# ra8875_ez80_2_1.net
KiCad netlist of a schematic drawn in EAGLE
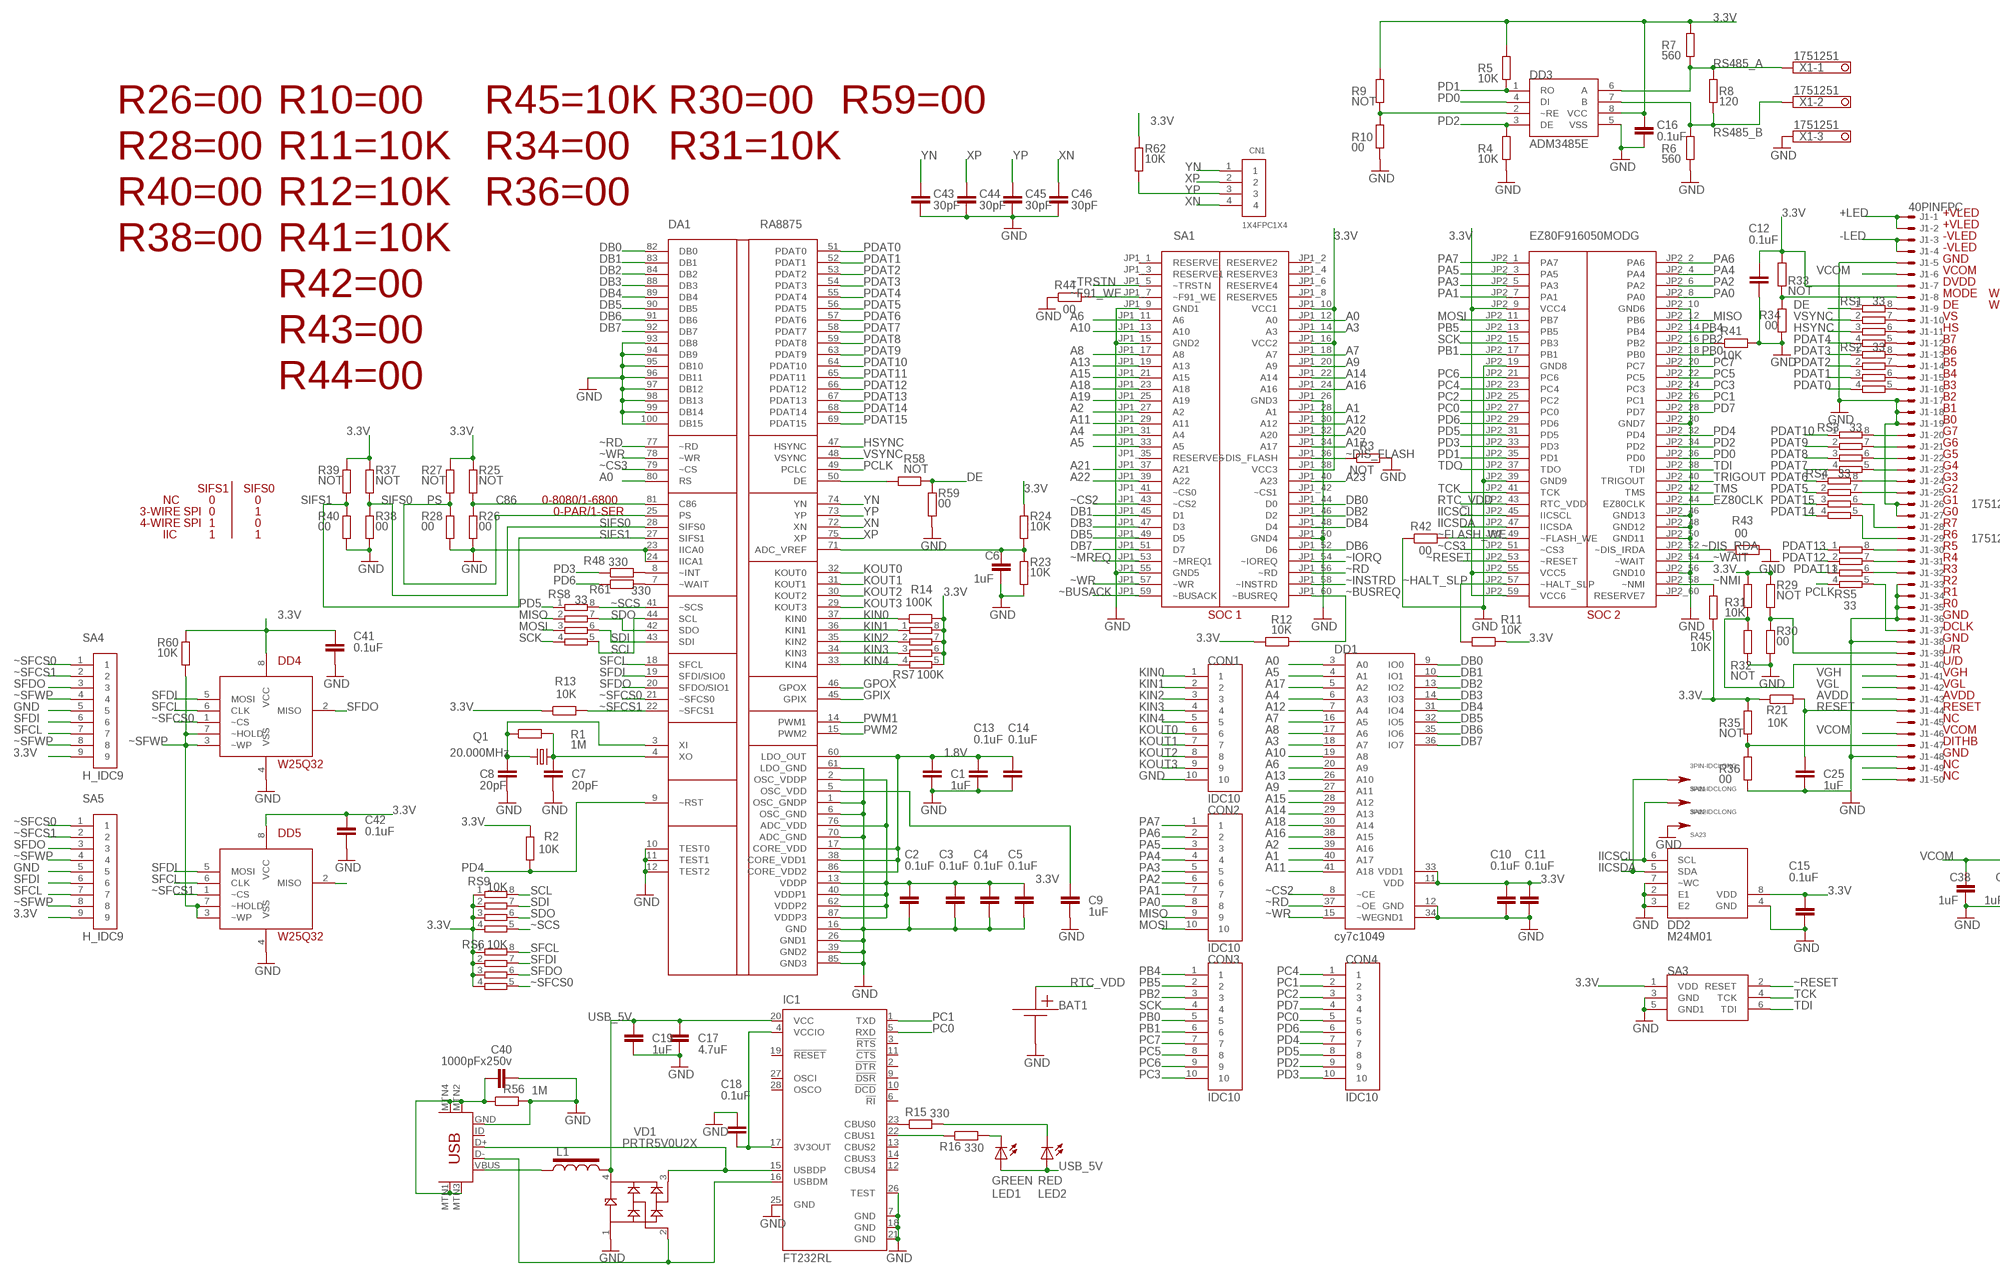
[diagram p0: schematic, sheet 1, part 1 of 2]
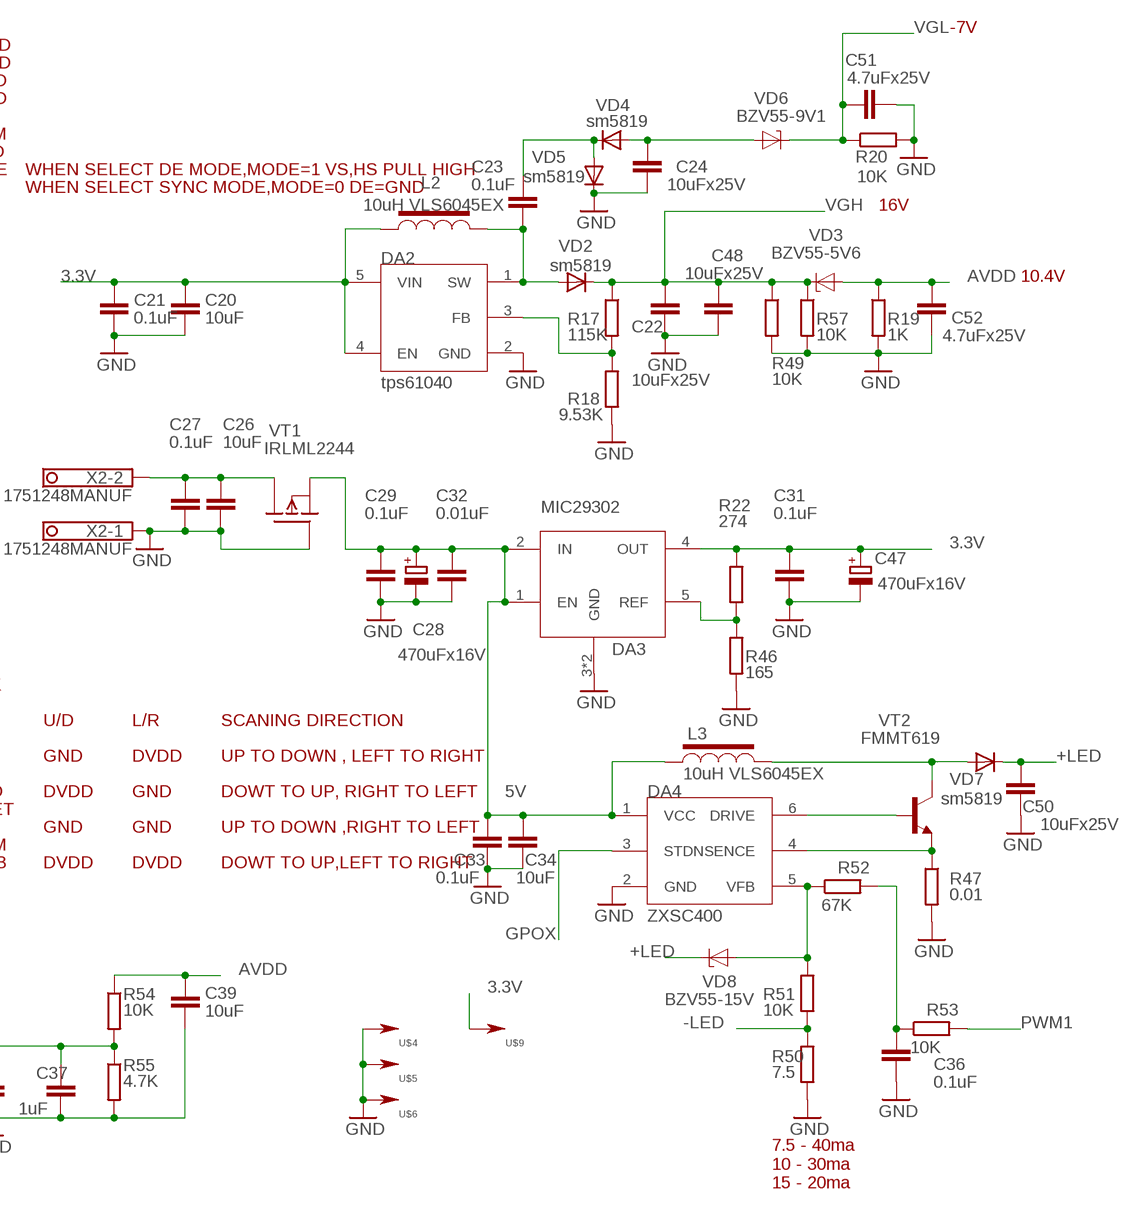
[diagram p1: schematic, sheet 1, part 2 of 2]

(export (version "E")
  (design (tool "Eeschema 10.0.6"))
  (components
    (comp (ref "BAT1")
      (value "EECF5R5U155")
      (footprint "eagle-import:EECF5R5U155")
      (libsource (lib "eagle-import") (part "EECF5R5U155"))
    )
    (comp (ref "C1")
      (value "1uF")
      (footprint "eagle-import:C0603")
      (libsource (lib "eagle-import") (part "C-EUC0603"))
    )
    (comp (ref "C2")
      (value "0.1uF")
      (footprint "eagle-import:C0603")
      (libsource (lib "eagle-import") (part "C-EUC0603"))
    )
    (comp (ref "C3")
      (value "0.1uF")
      (footprint "eagle-import:C0603")
      (libsource (lib "eagle-import") (part "C-EUC0603"))
    )
    (comp (ref "C4")
      (value "0.1uF")
      (footprint "eagle-import:C0603")
      (libsource (lib "eagle-import") (part "C-EUC0603"))
    )
    (comp (ref "C5")
      (value "0.1uF")
      (footprint "eagle-import:C0603")
      (libsource (lib "eagle-import") (part "C-EUC0603"))
    )
    (comp (ref "C6")
      (value "1uF")
      (footprint "eagle-import:C0603")
      (libsource (lib "eagle-import") (part "C-EUC0603"))
    )
    (comp (ref "C7")
      (value "20pF")
      (footprint "eagle-import:C0805")
      (libsource (lib "eagle-import") (part "C-EUC0805"))
    )
    (comp (ref "C8")
      (value "20pF")
      (footprint "eagle-import:C0805")
      (libsource (lib "eagle-import") (part "C-EUC0805"))
    )
    (comp (ref "C9")
      (value "1uF")
      (footprint "eagle-import:C0603")
      (libsource (lib "eagle-import") (part "C-EUC0603"))
    )
    (comp (ref "C10")
      (value "0.1uF")
      (footprint "eagle-import:C0603")
      (libsource (lib "eagle-import") (part "C-EUC0603"))
    )
    (comp (ref "C11")
      (value "0.1uF")
      (footprint "eagle-import:C0603")
      (libsource (lib "eagle-import") (part "C-EUC0603"))
    )
    (comp (ref "C12")
      (value "0.1uF")
      (footprint "eagle-import:C0603")
      (libsource (lib "eagle-import") (part "C-EUC0603"))
    )
    (comp (ref "C13")
      (value "0.1uF")
      (footprint "eagle-import:C0603")
      (libsource (lib "eagle-import") (part "C-EUC0603"))
    )
    (comp (ref "C14")
      (value "0.1uF")
      (footprint "eagle-import:C0603")
      (libsource (lib "eagle-import") (part "C-EUC0603"))
    )
    (comp (ref "C15")
      (value "0.1uF")
      (footprint "eagle-import:C0603")
      (libsource (lib "eagle-import") (part "C-EUC0603"))
    )
    (comp (ref "C16")
      (value "0.1uF")
      (footprint "eagle-import:C0603")
      (libsource (lib "eagle-import") (part "C-EUC0603"))
    )
    (comp (ref "C17")
      (value "4.7uF")
      (footprint "eagle-import:C0805")
      (libsource (lib "eagle-import") (part "C-EUC0805"))
    )
    (comp (ref "C18")
      (value "0.1uF")
      (footprint "eagle-import:C0603")
      (libsource (lib "eagle-import") (part "C-EUC0603"))
    )
    (comp (ref "C19")
      (value "1uF")
      (footprint "eagle-import:C0603")
      (libsource (lib "eagle-import") (part "C-EUC0603"))
    )
    (comp (ref "C20")
      (value "10uF")
      (footprint "eagle-import:C1206")
      (libsource (lib "eagle-import") (part "C-EUC1206"))
    )
    (comp (ref "C21")
      (value "0.1uF")
      (footprint "eagle-import:C0805")
      (libsource (lib "eagle-import") (part "C-EUC0805"))
    )
    (comp (ref "C22")
      (value "10uFx25V")
      (footprint "eagle-import:C1206")
      (libsource (lib "eagle-import") (part "C-EUC1206"))
    )
    (comp (ref "C23")
      (value "0.1uF")
      (footprint "eagle-import:C1206")
      (libsource (lib "eagle-import") (part "C-EUC1206"))
    )
    (comp (ref "C24")
      (value "10uFx25V")
      (footprint "eagle-import:C1206")
      (libsource (lib "eagle-import") (part "C-EUC1206"))
    )
    (comp (ref "C25")
      (value "1uF")
      (footprint "eagle-import:C0603")
      (libsource (lib "eagle-import") (part "C-EUC0603"))
    )
    (comp (ref "C26")
      (value "10uF")
      (footprint "eagle-import:C1206")
      (libsource (lib "eagle-import") (part "C-EUC1206"))
    )
    (comp (ref "C27")
      (value "0.1uF")
      (footprint "eagle-import:C0805")
      (libsource (lib "eagle-import") (part "C-EUC0805"))
    )
    (comp (ref "C28")
      (value "470uFx16V")
      (footprint "eagle-import:SMC_D")
      (libsource (lib "eagle-import") (part "CPOL-EUSMCD"))
    )
    (comp (ref "C29")
      (value "0.1uF")
      (footprint "eagle-import:C0805")
      (libsource (lib "eagle-import") (part "C-EUC0805"))
    )
    (comp (ref "C31")
      (value "0.1uF")
      (footprint "eagle-import:C0805")
      (libsource (lib "eagle-import") (part "C-EUC0805"))
    )
    (comp (ref "C32")
      (value "0.01uF")
      (footprint "eagle-import:C0805")
      (libsource (lib "eagle-import") (part "C-EUC0805"))
    )
    (comp (ref "C33")
      (value "0.1uF")
      (footprint "eagle-import:C0805")
      (libsource (lib "eagle-import") (part "C-EUC0805"))
    )
    (comp (ref "C34")
      (value "10uF")
      (footprint "eagle-import:C1206")
      (libsource (lib "eagle-import") (part "C-EUC1206"))
    )
    (comp (ref "C36")
      (value "0.1uF")
      (footprint "eagle-import:C0805")
      (libsource (lib "eagle-import") (part "C-EUC0805"))
    )
    (comp (ref "C37")
      (value "1uF")
      (footprint "eagle-import:C0603")
      (libsource (lib "eagle-import") (part "C-EUC0603"))
    )
    (comp (ref "C38")
      (value "1uF")
      (footprint "eagle-import:C0603")
      (libsource (lib "eagle-import") (part "C-EUC0603"))
    )
    (comp (ref "C39")
      (value "10uF")
      (footprint "eagle-import:C1206")
      (libsource (lib "eagle-import") (part "C-EUC1206"))
    )
    (comp (ref "C40")
      (value "1000pFx250v")
      (footprint "eagle-import:C1812")
      (libsource (lib "eagle-import") (part "C-EUC1812"))
    )
    (comp (ref "C41")
      (value "0.1uF")
      (footprint "eagle-import:C0603")
      (libsource (lib "eagle-import") (part "C-EUC0603"))
    )
    (comp (ref "C42")
      (value "0.1uF")
      (footprint "eagle-import:C0603")
      (libsource (lib "eagle-import") (part "C-EUC0603"))
    )
    (comp (ref "C43")
      (value "30pF")
      (footprint "eagle-import:C0603")
      (libsource (lib "eagle-import") (part "C-EUC0603"))
    )
    (comp (ref "C44")
      (value "30pF")
      (footprint "eagle-import:C0603")
      (libsource (lib "eagle-import") (part "C-EUC0603"))
    )
    (comp (ref "C45")
      (value "30pF")
      (footprint "eagle-import:C0603")
      (libsource (lib "eagle-import") (part "C-EUC0603"))
    )
    (comp (ref "C46")
      (value "30pF")
      (footprint "eagle-import:C0603")
      (libsource (lib "eagle-import") (part "C-EUC0603"))
    )
    (comp (ref "C47")
      (value "470uFx16V")
      (footprint "eagle-import:SMC_D")
      (libsource (lib "eagle-import") (part "CPOL-EUSMCD"))
    )
    (comp (ref "C48")
      (value "10uFx25V")
      (footprint "eagle-import:C1206")
      (libsource (lib "eagle-import") (part "C-EUC1206"))
    )
    (comp (ref "C50")
      (value "10uFx25V")
      (footprint "eagle-import:C1206")
      (libsource (lib "eagle-import") (part "C-EUC1206"))
    )
    (comp (ref "C51")
      (value "4.7uFx25V")
      (footprint "eagle-import:C1206")
      (libsource (lib "eagle-import") (part "C-EUC1206"))
    )
    (comp (ref "C52")
      (value "4.7uFx25V")
      (footprint "eagle-import:C1206")
      (libsource (lib "eagle-import") (part "C-EUC1206"))
    )
    (comp (ref "CN1")
      (value "1X4FPC1X4")
      (footprint "eagle-import:FPC_1MM-4")
      (libsource (lib "eagle-import") (part "1X4FPC1X4"))
    )
    (comp (ref "CON1")
      (value "IDC10")
      (footprint "eagle-import:IDC10")
      (libsource (lib "eagle-import") (part "IDC10"))
    )
    (comp (ref "CON2")
      (value "IDC10")
      (footprint "eagle-import:IDC10")
      (libsource (lib "eagle-import") (part "IDC10"))
    )
    (comp (ref "CON3")
      (value "IDC10")
      (footprint "eagle-import:IDC10")
      (libsource (lib "eagle-import") (part "IDC10"))
    )
    (comp (ref "CON4")
      (value "IDC10")
      (footprint "eagle-import:IDC10")
      (libsource (lib "eagle-import") (part "IDC10"))
    )
    (comp (ref "DA1")
      (value "RA8875")
      (footprint "eagle-import:LQFP100")
      (libsource (lib "eagle-import") (part "RA8875"))
    )
    (comp (ref "DA2")
      (value "tps61040")
      (footprint "eagle-import:SOT23-5L")
      (libsource (lib "eagle-import") (part "TPS61040"))
    )
    (comp (ref "DA3")
      (value "MIC29302")
      (footprint "eagle-import:TO263-5")
      (libsource (lib "eagle-import") (part "MIC29302TO263-5"))
    )
    (comp (ref "DA4")
      (value "ZXSC400")
      (footprint "eagle-import:SOT23-6L")
      (libsource (lib "eagle-import") (part "ZXSC400LONG"))
    )
    (comp (ref "DD1")
      (value "cy7c1049")
      (footprint "eagle-import:TSOP_Z44_II")
      (libsource (lib "eagle-import") (part "CY7C1049DV33"))
    )
    (comp (ref "DD2")
      (value "M24M01")
      (footprint "eagle-import:SOIC8")
      (libsource (lib "eagle-import") (part "M24M01SOIC8"))
    )
    (comp (ref "DD3")
      (value "ADM3485E")
      (footprint "eagle-import:SO8")
      (libsource (lib "eagle-import") (part "ADM3485ESOIC8"))
    )
    (comp (ref "DD4")
      (value "W25Q32")
      (footprint "eagle-import:SOIC-208")
      (libsource (lib "eagle-import") (part "W25Q32SOIC208"))
    )
    (comp (ref "DD5")
      (value "W25Q32")
      (footprint "eagle-import:SOIC-208")
      (libsource (lib "eagle-import") (part "W25Q32SOIC208"))
    )
    (comp (ref "IC1")
      (value "FT232RL")
      (footprint "eagle-import:SSOP28")
      (libsource (lib "eagle-import") (part "FT232RL"))
    )
    (comp (ref "J1")
      (value "40PINFPC")
      (footprint "eagle-import:4-1734839-0")
      (libsource (lib "eagle-import") (part "40PINFPC"))
    )
    (comp (ref "L1")
      (value "USB_INDUCTOR")
      (footprint "eagle-import:R0805")
      (libsource (lib "eagle-import") (part "USB_INDUCTOR"))
    )
    (comp (ref "L2")
      (value "10uH VLS6045EX")
      (footprint "eagle-import:VLS6045")
      (libsource (lib "eagle-import") (part "INDUCTOR6045"))
    )
    (comp (ref "L3")
      (value "10uH VLS6045EX")
      (footprint "eagle-import:VLS6045")
      (libsource (lib "eagle-import") (part "INDUCTOR6045"))
    )
    (comp (ref "LED1")
      (value "GREEN")
      (footprint "eagle-import:CHIPLED_1206")
      (libsource (lib "eagle-import") (part "LEDCHIPLED_1206"))
    )
    (comp (ref "LED2")
      (value "RED")
      (footprint "eagle-import:CHIPLED_1206")
      (libsource (lib "eagle-import") (part "LEDCHIPLED_1206"))
    )
    (comp (ref "Q1")
      (value "20.000MHz")
      (footprint "eagle-import:HC49U70")
      (libsource (lib "eagle-import") (part "CRYSTALHC49U70"))
    )
    (comp (ref "R1")
      (value "1M")
      (footprint "eagle-import:R0603")
      (libsource (lib "eagle-import") (part "R-EU_R0603"))
    )
    (comp (ref "R2")
      (value "10K")
      (footprint "eagle-import:R0603")
      (libsource (lib "eagle-import") (part "R-EU_R0603"))
    )
    (comp (ref "R3")
      (value "NOT")
      (footprint "eagle-import:R0603")
      (libsource (lib "eagle-import") (part "R-EU_R0603"))
    )
    (comp (ref "R4")
      (value "10K")
      (footprint "eagle-import:R0603")
      (libsource (lib "eagle-import") (part "R-EU_R0603"))
    )
    (comp (ref "R5")
      (value "10K")
      (footprint "eagle-import:R0603")
      (libsource (lib "eagle-import") (part "R-EU_R0603"))
    )
    (comp (ref "R6")
      (value "560")
      (footprint "eagle-import:R0603")
      (libsource (lib "eagle-import") (part "R-EU_R0603"))
    )
    (comp (ref "R7")
      (value "560")
      (footprint "eagle-import:R0603")
      (libsource (lib "eagle-import") (part "R-EU_R0603"))
    )
    (comp (ref "R8")
      (value "120")
      (footprint "eagle-import:R0603")
      (libsource (lib "eagle-import") (part "R-EU_R0603"))
    )
    (comp (ref "R9")
      (value "NOT")
      (footprint "eagle-import:R0603")
      (libsource (lib "eagle-import") (part "R-EU_R0603"))
    )
    (comp (ref "R10")
      (value "00")
      (footprint "eagle-import:R0603")
      (libsource (lib "eagle-import") (part "R-EU_R0603"))
    )
    (comp (ref "R11")
      (value "10K")
      (footprint "eagle-import:R0603")
      (libsource (lib "eagle-import") (part "R-EU_R0603"))
    )
    (comp (ref "R12")
      (value "10K")
      (footprint "eagle-import:R0603")
      (libsource (lib "eagle-import") (part "R-EU_R0603"))
    )
    (comp (ref "R13")
      (value "10K")
      (footprint "eagle-import:R0603")
      (libsource (lib "eagle-import") (part "R-EU_R0603"))
    )
    (comp (ref "R14")
      (value "100K")
      (footprint "eagle-import:R0603")
      (libsource (lib "eagle-import") (part "R-EU_R0603"))
    )
    (comp (ref "R15")
      (value "330")
      (footprint "eagle-import:R0603")
      (libsource (lib "eagle-import") (part "R-EU_R0603"))
    )
    (comp (ref "R16")
      (value "330")
      (footprint "eagle-import:R0603")
      (libsource (lib "eagle-import") (part "R-EU_R0603"))
    )
    (comp (ref "R17")
      (value "115K")
      (footprint "eagle-import:R0805")
      (libsource (lib "eagle-import") (part "R-EU_R0805"))
    )
    (comp (ref "R18")
      (value "9.53K")
      (footprint "eagle-import:R0805")
      (libsource (lib "eagle-import") (part "R-EU_R0805"))
    )
    (comp (ref "R19")
      (value "1K")
      (footprint "eagle-import:R0805")
      (libsource (lib "eagle-import") (part "R-EU_R0805"))
    )
    (comp (ref "R20")
      (value "10K")
      (footprint "eagle-import:R0805")
      (libsource (lib "eagle-import") (part "R-EU_R0805"))
    )
    (comp (ref "R21")
      (value "10K")
      (footprint "eagle-import:R0603")
      (libsource (lib "eagle-import") (part "R-EU_R0603"))
    )
    (comp (ref "R22")
      (value "274")
      (footprint "eagle-import:R0805")
      (libsource (lib "eagle-import") (part "R-EU_R0805"))
    )
    (comp (ref "R23")
      (value "10K")
      (footprint "eagle-import:R0603")
      (libsource (lib "eagle-import") (part "R-EU_R0603"))
    )
    (comp (ref "R24")
      (value "10K")
      (footprint "eagle-import:R0603")
      (libsource (lib "eagle-import") (part "R-EU_R0603"))
    )
    (comp (ref "R25")
      (value "NOT")
      (footprint "eagle-import:R0603")
      (libsource (lib "eagle-import") (part "R-EU_R0603"))
    )
    (comp (ref "R26")
      (value "00")
      (footprint "eagle-import:R0603")
      (libsource (lib "eagle-import") (part "R-EU_R0603"))
    )
    (comp (ref "R27")
      (value "NOT")
      (footprint "eagle-import:R0603")
      (libsource (lib "eagle-import") (part "R-EU_R0603"))
    )
    (comp (ref "R28")
      (value "00")
      (footprint "eagle-import:R0603")
      (libsource (lib "eagle-import") (part "R-EU_R0603"))
    )
    (comp (ref "R29")
      (value "NOT")
      (footprint "eagle-import:R0603")
      (libsource (lib "eagle-import") (part "R-EU_R0603"))
    )
    (comp (ref "R30")
      (value "00")
      (footprint "eagle-import:R0603")
      (libsource (lib "eagle-import") (part "R-EU_R0603"))
    )
    (comp (ref "R31")
      (value "10K")
      (footprint "eagle-import:R0603")
      (libsource (lib "eagle-import") (part "R-EU_R0603"))
    )
    (comp (ref "R32")
      (value "NOT")
      (footprint "eagle-import:R0603")
      (libsource (lib "eagle-import") (part "R-EU_R0603"))
    )
    (comp (ref "R33")
      (value "NOT")
      (footprint "eagle-import:R0603")
      (libsource (lib "eagle-import") (part "R-EU_R0603"))
    )
    (comp (ref "R34")
      (value "00")
      (footprint "eagle-import:R0603")
      (libsource (lib "eagle-import") (part "R-EU_R0603"))
    )
    (comp (ref "R35")
      (value "NOT")
      (footprint "eagle-import:R0603")
      (libsource (lib "eagle-import") (part "R-EU_R0603"))
    )
    (comp (ref "R36")
      (value "00")
      (footprint "eagle-import:R0603")
      (libsource (lib "eagle-import") (part "R-EU_R0603"))
    )
    (comp (ref "R37")
      (value "NOT")
      (footprint "eagle-import:R0603")
      (libsource (lib "eagle-import") (part "R-EU_R0603"))
    )
    (comp (ref "R38")
      (value "00")
      (footprint "eagle-import:R0603")
      (libsource (lib "eagle-import") (part "R-EU_R0603"))
    )
    (comp (ref "R39")
      (value "NOT")
      (footprint "eagle-import:R0603")
      (libsource (lib "eagle-import") (part "R-EU_R0603"))
    )
    (comp (ref "R40")
      (value "00")
      (footprint "eagle-import:R0603")
      (libsource (lib "eagle-import") (part "R-EU_R0603"))
    )
    (comp (ref "R41")
      (value "10K")
      (footprint "eagle-import:R0603")
      (libsource (lib "eagle-import") (part "R-EU_R0603"))
    )
    (comp (ref "R42")
      (value "00")
      (footprint "eagle-import:R0603")
      (libsource (lib "eagle-import") (part "R-EU_R0603"))
    )
    (comp (ref "R43")
      (value "00")
      (footprint "eagle-import:R0603")
      (libsource (lib "eagle-import") (part "R-EU_R0603"))
    )
    (comp (ref "R44")
      (value "00")
      (footprint "eagle-import:R0603")
      (libsource (lib "eagle-import") (part "R-EU_R0603"))
    )
    (comp (ref "R45")
      (value "10K")
      (footprint "eagle-import:R0603")
      (libsource (lib "eagle-import") (part "R-EU_R0603"))
    )
    (comp (ref "R46")
      (value "165")
      (footprint "eagle-import:R0805")
      (libsource (lib "eagle-import") (part "R-EU_R0805"))
    )
    (comp (ref "R47")
      (value "0.01")
      (footprint "eagle-import:R2512")
      (libsource (lib "eagle-import") (part "R-EU_R2512"))
    )
    (comp (ref "R48")
      (value "330")
      (footprint "eagle-import:R0603")
      (libsource (lib "eagle-import") (part "R-EU_R0603"))
    )
    (comp (ref "R49")
      (value "10K")
      (footprint "eagle-import:R1206")
      (libsource (lib "eagle-import") (part "R-EU_R1206"))
    )
    (comp (ref "R50")
      (value "7.5")
      (footprint "eagle-import:R0805")
      (libsource (lib "eagle-import") (part "R-EU_R0805"))
    )
    (comp (ref "R51")
      (value "10K")
      (footprint "eagle-import:R0603")
      (libsource (lib "eagle-import") (part "R-EU_R0603"))
    )
    (comp (ref "R52")
      (value "67K")
      (footprint "eagle-import:R0603")
      (libsource (lib "eagle-import") (part "R-EU_R0603"))
    )
    (comp (ref "R53")
      (value "10K")
      (footprint "eagle-import:R0603")
      (libsource (lib "eagle-import") (part "R-EU_R0603"))
    )
    (comp (ref "R54")
      (value "10K")
      (footprint "eagle-import:R0603")
      (libsource (lib "eagle-import") (part "R-EU_R0603"))
    )
    (comp (ref "R55")
      (value "4.7K")
      (footprint "eagle-import:R0603")
      (libsource (lib "eagle-import") (part "R-EU_R0603"))
    )
    (comp (ref "R56")
      (value "1M")
      (footprint "eagle-import:R1206")
      (libsource (lib "eagle-import") (part "R-EU_R1206"))
    )
    (comp (ref "R57")
      (value "10K")
      (footprint "eagle-import:R1206")
      (libsource (lib "eagle-import") (part "R-EU_R1206"))
    )
    (comp (ref "R58")
      (value "NOT")
      (footprint "eagle-import:R0603")
      (libsource (lib "eagle-import") (part "R-EU_R0603"))
    )
    (comp (ref "R59")
      (value "00")
      (footprint "eagle-import:R0603")
      (libsource (lib "eagle-import") (part "R-EU_R0603"))
    )
    (comp (ref "R60")
      (value "10K")
      (footprint "eagle-import:R0603")
      (libsource (lib "eagle-import") (part "R-EU_R0603"))
    )
    (comp (ref "R61")
      (value "330")
      (footprint "eagle-import:R0603")
      (libsource (lib "eagle-import") (part "R-EU_R0603"))
    )
    (comp (ref "R62")
      (value "10K")
      (footprint "eagle-import:R0603")
      (libsource (lib "eagle-import") (part "R-EU_R0603"))
    )
    (comp (ref "RS1")
      (value "33")
      (footprint "eagle-import:CAY16-4")
      (libsource (lib "eagle-import") (part "MULTI_RESISRORCAY16-4"))
    )
    (comp (ref "RS2")
      (value "33")
      (footprint "eagle-import:CAY16-4")
      (libsource (lib "eagle-import") (part "MULTI_RESISRORCAY16-4"))
    )
    (comp (ref "RS3")
      (value "33")
      (footprint "eagle-import:CAY16-4")
      (libsource (lib "eagle-import") (part "MULTI_RESISRORCAY16-4"))
    )
    (comp (ref "RS4")
      (value "33")
      (footprint "eagle-import:CAY16-4")
      (libsource (lib "eagle-import") (part "MULTI_RESISRORCAY16-4"))
    )
    (comp (ref "RS5")
      (value "33")
      (footprint "eagle-import:CAY16-4")
      (libsource (lib "eagle-import") (part "MULTI_RESISRORCAY16-4"))
    )
    (comp (ref "RS6")
      (value "10K")
      (footprint "eagle-import:CAY16-4")
      (libsource (lib "eagle-import") (part "MULTI_RESISRORCAY16-4"))
    )
    (comp (ref "RS7")
      (value "100K")
      (footprint "eagle-import:CAY16-4")
      (libsource (lib "eagle-import") (part "MULTI_RESISRORCAY16-4"))
    )
    (comp (ref "RS8")
      (value "33")
      (footprint "eagle-import:CAY16-4")
      (libsource (lib "eagle-import") (part "MULTI_RESISRORCAY16-4"))
    )
    (comp (ref "RS9")
      (value "10K")
      (footprint "eagle-import:CAY16-4")
      (libsource (lib "eagle-import") (part "MULTI_RESISRORCAY16-4"))
    )
    (comp (ref "SA1")
      (value "EZ80F916050MODG")
      (footprint "eagle-import:EZ80F916050MODG")
      (libsource (lib "eagle-import") (part "EZ80F916050MODG"))
    )
    (comp (ref "SA2")
      (value "3PIN-IDCLONG")
      (footprint "eagle-import:3PIN-254")
      (libsource (lib "eagle-import") (part "3PIN-IDCLONG"))
    )
    (comp (ref "SA3")
      (value "ZPAKII")
      (footprint "eagle-import:ZPAKII")
      (libsource (lib "eagle-import") (part "ZPAKII"))
    )
    (comp (ref "SA4")
      (value "H_IDC9")
      (footprint "eagle-import:H_IDC8X1_27")
      (libsource (lib "eagle-import") (part "H_IDC9"))
    )
    (comp (ref "SA5")
      (value "H_IDC9")
      (footprint "eagle-import:H_IDC8X1_27")
      (libsource (lib "eagle-import") (part "H_IDC9"))
    )
    (comp (ref "U$3")
      (value "USB-MINIB-5PIN")
      (footprint "eagle-import:USB-MINIB")
      (libsource (lib "eagle-import") (part "USB-MINIB-5PIN"))
    )
    (comp (ref "U$4")
      (value "1-PIN2_54")
      (footprint "eagle-import:1_PIN_2_54")
      (libsource (lib "eagle-import") (part "1-PIN2_54"))
    )
    (comp (ref "U$5")
      (value "1-PIN2_54")
      (footprint "eagle-import:1_PIN_2_54")
      (libsource (lib "eagle-import") (part "1-PIN2_54"))
    )
    (comp (ref "U$6")
      (value "1-PIN2_54")
      (footprint "eagle-import:1_PIN_2_54")
      (libsource (lib "eagle-import") (part "1-PIN2_54"))
    )
    (comp (ref "U$9")
      (value "1-PIN2_54")
      (footprint "eagle-import:1_PIN_2_54")
      (libsource (lib "eagle-import") (part "1-PIN2_54"))
    )
    (comp (ref "VD1")
      (value "PRTR5V0U2X")
      (footprint "eagle-import:SOT143B")
      (libsource (lib "eagle-import") (part "PRTR5V0U2X"))
    )
    (comp (ref "VD2")
      (value "sm5819")
      (footprint "eagle-import:MELF-MLL41")
      (libsource (lib "eagle-import") (part "SM5819"))
    )
    (comp (ref "VD3")
      (value "BZV55-5V6")
      (footprint "eagle-import:STABILITRON")
      (libsource (lib "eagle-import") (part "STABILITRONSMD"))
    )
    (comp (ref "VD4")
      (value "sm5819")
      (footprint "eagle-import:MELF-MLL41")
      (libsource (lib "eagle-import") (part "SM5819"))
    )
    (comp (ref "VD5")
      (value "sm5819")
      (footprint "eagle-import:MELF-MLL41")
      (libsource (lib "eagle-import") (part "SM5819"))
    )
    (comp (ref "VD6")
      (value "BZV55-9V1")
      (footprint "eagle-import:STABILITRON")
      (libsource (lib "eagle-import") (part "STABILITRONSMD"))
    )
    (comp (ref "VD7")
      (value "sm5819")
      (footprint "eagle-import:MELF-MLL41")
      (libsource (lib "eagle-import") (part "SM5819"))
    )
    (comp (ref "VD8")
      (value "BZV55-15V")
      (footprint "eagle-import:STABILITRON")
      (libsource (lib "eagle-import") (part "STABILITRONSMD"))
    )
    (comp (ref "VT1")
      (value "IRLML2244")
      (footprint "eagle-import:SOT23")
      (libsource (lib "eagle-import") (part "P-MOSFETSOT23"))
    )
    (comp (ref "VT2")
      (value "FMMT619")
      (footprint "eagle-import:SOT23-BEC")
      (libsource (lib "eagle-import") (part "-NPN-SOT23-BECBC847B"))
    )
    (comp (ref "X1")
      (value "1751251")
      (footprint "eagle-import:1751251")
      (libsource (lib "eagle-import") (part "1751251"))
    )
    (comp (ref "X2")
      (value "1751248MANUF")
      (footprint "eagle-import:1751248")
      (libsource (lib "eagle-import") (part "1751248MANUF"))
    )
  )
  (nets
    (net (code "1") (name "/+LED") (class "Default")
      (node (ref "C50") (pin "1") (pinfunction "1_1") (pintype "passive"))
      (node (ref "J1") (pin "1") (pinfunction "MSV_1") (pintype "passive"))
      (node (ref "J1") (pin "2") (pinfunction "MS_2") (pintype "passive"))
      (node (ref "VD7") (pin "C") (pinfunction "C_C") (pintype "passive"))
      (node (ref "VD8") (pin "C") (pinfunction "C_C") (pintype "passive"))
    )
    (net (code "2") (name "/-LED") (class "Default")
      (node (ref "J1") (pin "3") (pinfunction "MS_3") (pintype "passive"))
      (node (ref "J1") (pin "4") (pinfunction "MS_4") (pintype "passive"))
      (node (ref "R50") (pin "1") (pinfunction "1_1") (pintype "passive"))
      (node (ref "R51") (pin "2") (pinfunction "2_2") (pintype "passive"))
    )
    (net (code "3") (name "/1.8V") (class "Default")
      (node (ref "C1") (pin "1") (pinfunction "1_1") (pintype "passive"))
      (node (ref "C13") (pin "1") (pinfunction "1_1") (pintype "passive"))
      (node (ref "C14") (pin "1") (pinfunction "1_1") (pintype "passive"))
      (node (ref "DA1") (pin "17") (pinfunction "CORE_VDD_17") (pintype "power_in"))
      (node (ref "DA1") (pin "38") (pinfunction "CORE_VDD1_38") (pintype "power_in"))
      (node (ref "DA1") (pin "60") (pinfunction "LDO_OUT_60") (pintype "power_in"))
      (node (ref "DA1") (pin "86") (pinfunction "CORE_VDD2_86") (pintype "power_in"))
    )
    (net (code "4") (name "/3.3V") (class "Default")
      (node (ref "C10") (pin "1") (pinfunction "1_1") (pintype "passive"))
      (node (ref "C11") (pin "1") (pinfunction "1_1") (pintype "passive"))
      (node (ref "C12") (pin "1") (pinfunction "1_1") (pintype "passive"))
      (node (ref "C15") (pin "1") (pinfunction "1_1") (pintype "passive"))
      (node (ref "C16") (pin "1") (pinfunction "1_1") (pintype "passive"))
      (node (ref "C2") (pin "1") (pinfunction "1_1") (pintype "passive"))
      (node (ref "C20") (pin "1") (pinfunction "1_1") (pintype "passive"))
      (node (ref "C21") (pin "1") (pinfunction "1_1") (pintype "passive"))
      (node (ref "C3") (pin "1") (pinfunction "1_1") (pintype "passive"))
      (node (ref "C31") (pin "1") (pinfunction "1_1") (pintype "passive"))
      (node (ref "C4") (pin "1") (pinfunction "1_1") (pintype "passive"))
      (node (ref "C41") (pin "1") (pinfunction "1_1") (pintype "passive"))
      (node (ref "C42") (pin "1") (pinfunction "1_1") (pintype "passive"))
      (node (ref "C47") (pin "+") (pinfunction "+_+") (pintype "passive"))
      (node (ref "C5") (pin "1") (pinfunction "1_1") (pintype "passive"))
      (node (ref "DA1") (pin "13") (pinfunction "VDDP_13") (pintype "power_in"))
      (node (ref "DA1") (pin "2") (pinfunction "OSC_VDDP_2") (pintype "power_in"))
      (node (ref "DA1") (pin "40") (pinfunction "VDDP1_40") (pintype "power_in"))
      (node (ref "DA1") (pin "62") (pinfunction "VDDP2_62") (pintype "power_in"))
      (node (ref "DA1") (pin "76") (pinfunction "ADC_VDD_76") (pintype "power_in"))
      (node (ref "DA1") (pin "87") (pinfunction "VDDP3_87") (pintype "power_in"))
      (node (ref "DA2") (pin "4") (pinfunction "EN_4") (pintype "input"))
      (node (ref "DA2") (pin "5") (pinfunction "VIN_5") (pintype "power_in"))
      (node (ref "DA3") (pin "4") (pinfunction "OUT_4") (pintype "power_in"))
      (node (ref "DD1") (pin "11") (pinfunction "VDD_11") (pintype "power_in"))
      (node (ref "DD1") (pin "33") (pinfunction "VDD1_33") (pintype "power_in"))
      (node (ref "DD2") (pin "8") (pinfunction "VDD_8") (pintype "power_in"))
      (node (ref "DD3") (pin "8") (pinfunction "VCC_8") (pintype "power_in"))
      (node (ref "DD4") (pin "8") (pinfunction "VCC_8") (pintype "power_in"))
      (node (ref "DD5") (pin "8") (pinfunction "VCC_8") (pintype "power_in"))
      (node (ref "J1") (pin "7") (pinfunction "MS_7") (pintype "passive"))
      (node (ref "L2") (pin "P$1") (pinfunction "L1_P$1") (pintype "passive"))
      (node (ref "R11") (pin "1") (pinfunction "1_1") (pintype "passive"))
      (node (ref "R12") (pin "2") (pinfunction "2_2") (pintype "passive"))
      (node (ref "R13") (pin "1") (pinfunction "1_1") (pintype "passive"))
      (node (ref "R14") (pin "2") (pinfunction "2_2") (pintype "passive"))
      (node (ref "R2") (pin "2") (pinfunction "2_2") (pintype "passive"))
      (node (ref "R21") (pin "1") (pinfunction "1_1") (pintype "passive"))
      (node (ref "R22") (pin "1") (pinfunction "1_1") (pintype "passive"))
      (node (ref "R24") (pin "1") (pinfunction "1_1") (pintype "passive"))
      (node (ref "R25") (pin "1") (pinfunction "1_1") (pintype "passive"))
      (node (ref "R27") (pin "1") (pinfunction "1_1") (pintype "passive"))
      (node (ref "R29") (pin "1") (pinfunction "1_1") (pintype "passive"))
      (node (ref "R31") (pin "1") (pinfunction "1_1") (pintype "passive"))
      (node (ref "R33") (pin "1") (pinfunction "1_1") (pintype "passive"))
      (node (ref "R35") (pin "1") (pinfunction "1_1") (pintype "passive"))
      (node (ref "R37") (pin "1") (pinfunction "1_1") (pintype "passive"))
      (node (ref "R39") (pin "1") (pinfunction "1_1") (pintype "passive"))
      (node (ref "R45") (pin "2") (pinfunction "2_2") (pintype "passive"))
      (node (ref "R5") (pin "1") (pinfunction "1_1") (pintype "passive"))
      (node (ref "R60") (pin "1") (pinfunction "1_1") (pintype "passive"))
      (node (ref "R62") (pin "1") (pinfunction "1_1") (pintype "passive"))
      (node (ref "R7") (pin "1") (pinfunction "1_1") (pintype "passive"))
      (node (ref "R9") (pin "1") (pinfunction "1_1") (pintype "passive"))
      (node (ref "RS6") (pin "1") (pinfunction "1_1") (pintype "passive"))
      (node (ref "RS6") (pin "2") (pinfunction "2_2") (pintype "passive"))
      (node (ref "RS6") (pin "3") (pinfunction "3_3") (pintype "passive"))
      (node (ref "RS6") (pin "4") (pinfunction "4_4") (pintype "passive"))
      (node (ref "RS7") (pin "5") (pinfunction "5_5") (pintype "passive"))
      (node (ref "RS7") (pin "6") (pinfunction "6_6") (pintype "passive"))
      (node (ref "RS7") (pin "7") (pinfunction "7_7") (pintype "passive"))
      (node (ref "RS7") (pin "8") (pinfunction "8_8") (pintype "passive"))
      (node (ref "RS9") (pin "1") (pinfunction "1_1") (pintype "passive"))
      (node (ref "RS9") (pin "2") (pinfunction "2_2") (pintype "passive"))
      (node (ref "RS9") (pin "3") (pinfunction "3_3") (pintype "passive"))
      (node (ref "RS9") (pin "4") (pinfunction "4_4") (pintype "passive"))
      (node (ref "SA1") (pin "JP1_10") (pinfunction "VCC1_JP1_10") (pintype "power_in"))
      (node (ref "SA1") (pin "JP1_16") (pinfunction "VCC2_JP1_16") (pintype "power_in"))
      (node (ref "SA1") (pin "JP1_38") (pinfunction "VCC3_JP1_38") (pintype "power_in"))
      (node (ref "SA1") (pin "JP2_55") (pinfunction "VCC5_JP2_55") (pintype "power_in"))
      (node (ref "SA1") (pin "JP2_59") (pinfunction "VCC6_JP2_59") (pintype "power_in"))
      (node (ref "SA1") (pin "JP2_9") (pinfunction "VCC4_JP2_9") (pintype "power_in"))
      (node (ref "SA3") (pin "1") (pinfunction "VDD_1") (pintype "power_in"))
      (node (ref "SA4") (pin "9") (pinfunction "9_9") (pintype "bidirectional"))
      (node (ref "SA5") (pin "9") (pinfunction "9_9") (pintype "bidirectional"))
      (node (ref "U$9") (pin "P$1") (pinfunction "S_P$1") (pintype "passive"))
    )
    (net (code "5") (name "/5V") (class "Default")
      (node (ref "C28") (pin "+") (pinfunction "+_+") (pintype "passive"))
      (node (ref "C29") (pin "1") (pinfunction "1_1") (pintype "passive"))
      (node (ref "C32") (pin "1") (pinfunction "1_1") (pintype "passive"))
      (node (ref "C33") (pin "1") (pinfunction "1_1") (pintype "passive"))
      (node (ref "C34") (pin "1") (pinfunction "1_1") (pintype "passive"))
      (node (ref "DA3") (pin "1") (pinfunction "EN_1") (pintype "input"))
      (node (ref "DA3") (pin "2") (pinfunction "IN_2") (pintype "power_in"))
      (node (ref "DA4") (pin "1") (pinfunction "VCC_1") (pintype "power_in"))
      (node (ref "L3") (pin "P$1") (pinfunction "L1_P$1") (pintype "passive"))
      (node (ref "VT1") (pin "2") (pinfunction "S_2") (pintype "passive"))
    )
    (net (code "6") (name "/A0") (class "Default")
      (node (ref "DA1") (pin "80") (pinfunction "RS_80") (pintype "input"))
      (node (ref "DD1") (pin "3") (pinfunction "A0_3") (pintype "input"))
      (node (ref "SA1") (pin "JP1_12") (pinfunction "A0_JP1_12") (pintype "bidirectional"))
    )
    (net (code "7") (name "/A1") (class "Default")
      (node (ref "DD1") (pin "40") (pinfunction "A17_40") (pintype "input"))
      (node (ref "SA1") (pin "JP1_28") (pinfunction "A1_JP1_28") (pintype "bidirectional"))
    )
    (net (code "8") (name "/A2") (class "Default")
      (node (ref "DD1") (pin "39") (pinfunction "A16_39") (pintype "input"))
      (node (ref "SA1") (pin "JP1_27") (pinfunction "A2_JP1_27") (pintype "bidirectional"))
    )
    (net (code "9") (name "/A3") (class "Default")
      (node (ref "DD1") (pin "18") (pinfunction "A7_18") (pintype "input"))
      (node (ref "SA1") (pin "JP1_14") (pinfunction "A3_JP1_14") (pintype "bidirectional"))
    )
    (net (code "10") (name "/A4") (class "Default")
      (node (ref "DD1") (pin "6") (pinfunction "A3_6") (pintype "input"))
      (node (ref "SA1") (pin "JP1_31") (pinfunction "A4_JP1_31") (pintype "bidirectional"))
    )
    (net (code "11") (name "/A5") (class "Default")
      (node (ref "DD1") (pin "4") (pinfunction "A1_4") (pintype "input"))
      (node (ref "SA1") (pin "JP1_33") (pinfunction "A5_JP1_33") (pintype "bidirectional"))
    )
    (net (code "12") (name "/A6") (class "Default")
      (node (ref "DD1") (pin "20") (pinfunction "A9_20") (pintype "input"))
      (node (ref "SA1") (pin "JP1_11") (pinfunction "A6_JP1_11") (pintype "bidirectional"))
    )
    (net (code "13") (name "/A7") (class "Default")
      (node (ref "DD1") (pin "16") (pinfunction "A5_16") (pintype "input"))
      (node (ref "SA1") (pin "JP1_18") (pinfunction "A7_JP1_18") (pintype "bidirectional"))
    )
    (net (code "14") (name "/A8") (class "Default")
      (node (ref "DD1") (pin "17") (pinfunction "A6_17") (pintype "input"))
      (node (ref "SA1") (pin "JP1_17") (pinfunction "A8_JP1_17") (pintype "bidirectional"))
    )
    (net (code "15") (name "/A9") (class "Default")
      (node (ref "DD1") (pin "27") (pinfunction "A11_27") (pintype "input"))
      (node (ref "SA1") (pin "JP1_20") (pinfunction "A9_JP1_20") (pintype "bidirectional"))
    )
    (net (code "16") (name "/A10") (class "Default")
      (node (ref "DD1") (pin "19") (pinfunction "A8_19") (pintype "input"))
      (node (ref "SA1") (pin "JP1_13") (pinfunction "A10_JP1_13") (pintype "bidirectional"))
    )
    (net (code "17") (name "/A11") (class "Default")
      (node (ref "DD1") (pin "41") (pinfunction "A18_41") (pintype "input"))
      (node (ref "SA1") (pin "JP1_29") (pinfunction "A11_JP1_29") (pintype "bidirectional"))
    )
    (net (code "18") (name "/A12") (class "Default")
      (node (ref "DD1") (pin "7") (pinfunction "A4_7") (pintype "input"))
      (node (ref "SA1") (pin "JP1_30") (pinfunction "A12_JP1_30") (pintype "bidirectional"))
    )
    (net (code "19") (name "/A13") (class "Default")
      (node (ref "DD1") (pin "26") (pinfunction "A10_26") (pintype "input"))
      (node (ref "SA1") (pin "JP1_19") (pinfunction "A13_JP1_19") (pintype "bidirectional"))
    )
    (net (code "20") (name "/A14") (class "Default")
      (node (ref "DD1") (pin "29") (pinfunction "A13_29") (pintype "input"))
      (node (ref "SA1") (pin "JP1_22") (pinfunction "A14_JP1_22") (pintype "bidirectional"))
    )
    (net (code "21") (name "/A15") (class "Default")
      (node (ref "DD1") (pin "28") (pinfunction "A12_28") (pintype "input"))
      (node (ref "SA1") (pin "JP1_21") (pinfunction "A15_JP1_21") (pintype "bidirectional"))
    )
    (net (code "22") (name "/A16") (class "Default")
      (node (ref "DD1") (pin "38") (pinfunction "A15_38") (pintype "input"))
      (node (ref "SA1") (pin "JP1_24") (pinfunction "A16_JP1_24") (pintype "bidirectional"))
    )
    (net (code "23") (name "/A17") (class "Default")
      (node (ref "DD1") (pin "5") (pinfunction "A2_5") (pintype "input"))
      (node (ref "SA1") (pin "JP1_34") (pinfunction "A17_JP1_34") (pintype "bidirectional"))
    )
    (net (code "24") (name "/A18") (class "Default")
      (node (ref "DD1") (pin "30") (pinfunction "A14_30") (pintype "input"))
      (node (ref "SA1") (pin "JP1_23") (pinfunction "A18_JP1_23") (pintype "bidirectional"))
    )
    (net (code "25") (name "/A19") (class "Default")
      (node (ref "SA1") (pin "JP1_25") (pinfunction "A19_JP1_25") (pintype "bidirectional"))
    )
    (net (code "26") (name "/A20") (class "Default")
      (node (ref "SA1") (pin "JP1_32") (pinfunction "A20_JP1_32") (pintype "bidirectional"))
    )
    (net (code "27") (name "/A21") (class "Default")
      (node (ref "SA1") (pin "JP1_37") (pinfunction "A21_JP1_37") (pintype "bidirectional"))
    )
    (net (code "28") (name "/A22") (class "Default")
      (node (ref "SA1") (pin "JP1_39") (pinfunction "A22_JP1_39") (pintype "bidirectional"))
    )
    (net (code "29") (name "/A23") (class "Default")
      (node (ref "SA1") (pin "JP1_40") (pinfunction "A23_JP1_40") (pintype "bidirectional"))
    )
    (net (code "30") (name "/AVDD") (class "Default")
      (node (ref "C39") (pin "1") (pinfunction "1_1") (pintype "passive"))
      (node (ref "C52") (pin "1") (pinfunction "1_1") (pintype "passive"))
      (node (ref "J1") (pin "43") (pinfunction "MS_43") (pintype "passive"))
      (node (ref "R19") (pin "1") (pinfunction "1_1") (pintype "passive"))
      (node (ref "R54") (pin "1") (pinfunction "1_1") (pintype "passive"))
      (node (ref "VD3") (pin "A") (pinfunction "A_A") (pintype "passive"))
    )
    (net (code "31") (name "/C86") (class "Default")
      (node (ref "DA1") (pin "81") (pinfunction "C86_81") (pintype "input"))
      (node (ref "R25") (pin "2") (pinfunction "2_2") (pintype "passive"))
      (node (ref "R26") (pin "1") (pinfunction "1_1") (pintype "passive"))
    )
    (net (code "32") (name "/DB0") (class "Default")
      (node (ref "DA1") (pin "82") (pinfunction "DB0_82") (pintype "bidirectional"))
      (node (ref "DD1") (pin "9") (pinfunction "IO0_9") (pintype "bidirectional"))
      (node (ref "SA1") (pin "JP1_44") (pinfunction "D0_JP1_44") (pintype "bidirectional"))
    )
    (net (code "33") (name "/DB1") (class "Default")
      (node (ref "DA1") (pin "83") (pinfunction "DB1_83") (pintype "bidirectional"))
      (node (ref "DD1") (pin "10") (pinfunction "IO1_10") (pintype "bidirectional"))
      (node (ref "SA1") (pin "JP1_45") (pinfunction "D1_JP1_45") (pintype "bidirectional"))
    )
    (net (code "34") (name "/DB2") (class "Default")
      (node (ref "DA1") (pin "84") (pinfunction "DB2_84") (pintype "bidirectional"))
      (node (ref "DD1") (pin "13") (pinfunction "IO2_13") (pintype "bidirectional"))
      (node (ref "SA1") (pin "JP1_46") (pinfunction "D2_JP1_46") (pintype "bidirectional"))
    )
    (net (code "35") (name "/DB3") (class "Default")
      (node (ref "DA1") (pin "88") (pinfunction "DB3_88") (pintype "bidirectional"))
      (node (ref "DD1") (pin "14") (pinfunction "IO3_14") (pintype "bidirectional"))
      (node (ref "SA1") (pin "JP1_47") (pinfunction "D3_JP1_47") (pintype "bidirectional"))
    )
    (net (code "36") (name "/DB4") (class "Default")
      (node (ref "DA1") (pin "89") (pinfunction "DB4_89") (pintype "bidirectional"))
      (node (ref "DD1") (pin "31") (pinfunction "IO4_31") (pintype "bidirectional"))
      (node (ref "SA1") (pin "JP1_48") (pinfunction "D4_JP1_48") (pintype "bidirectional"))
    )
    (net (code "37") (name "/DB5") (class "Default")
      (node (ref "DA1") (pin "90") (pinfunction "DB5_90") (pintype "bidirectional"))
      (node (ref "DD1") (pin "32") (pinfunction "IO5_32") (pintype "bidirectional"))
      (node (ref "SA1") (pin "JP1_49") (pinfunction "D5_JP1_49") (pintype "bidirectional"))
    )
    (net (code "38") (name "/DB6") (class "Default")
      (node (ref "DA1") (pin "91") (pinfunction "DB6_91") (pintype "bidirectional"))
      (node (ref "DD1") (pin "35") (pinfunction "IO6_35") (pintype "bidirectional"))
      (node (ref "SA1") (pin "JP1_52") (pinfunction "D6_JP1_52") (pintype "bidirectional"))
    )
    (net (code "39") (name "/DB7") (class "Default")
      (node (ref "DA1") (pin "92") (pinfunction "DB7_92") (pintype "bidirectional"))
      (node (ref "DD1") (pin "36") (pinfunction "IO7_36") (pintype "bidirectional"))
      (node (ref "SA1") (pin "JP1_51") (pinfunction "D7_JP1_51") (pintype "bidirectional"))
    )
    (net (code "40") (name "/DE") (class "Default")
      (node (ref "R58") (pin "1") (pinfunction "1_1") (pintype "passive"))
      (node (ref "R59") (pin "1") (pinfunction "1_1") (pintype "passive"))
      (node (ref "RS1") (pin "1") (pinfunction "1_1") (pintype "passive"))
    )
    (net (code "41") (name "/EZ80CLK") (class "Default")
      (node (ref "SA1") (pin "JP2_44") (pinfunction "EZ80CLK_JP2_44") (pintype "output"))
    )
    (net (code "42") (name "/GPIX") (class "Default")
      (node (ref "DA1") (pin "45") (pinfunction "GPIX_45") (pintype "input"))
    )
    (net (code "43") (name "/GPOX") (class "Default")
      (node (ref "DA1") (pin "46") (pinfunction "GPOX_46") (pintype "output"))
      (node (ref "DA4") (pin "3") (pinfunction "STDN_3") (pintype "input"))
    )
    (net (code "44") (name "/HSYNC") (class "Default")
      (node (ref "DA1") (pin "47") (pinfunction "HSYNC_47") (pintype "output"))
      (node (ref "RS1") (pin "3") (pinfunction "3_3") (pintype "passive"))
    )
    (net (code "45") (name "/IICSCL") (class "Default")
      (node (ref "DD2") (pin "6") (pinfunction "SCL_6") (pintype "input"))
      (node (ref "SA1") (pin "JP2_45") (pinfunction "IICSCL_JP2_45") (pintype "bidirectional"))
      (node (ref "SA2") (pin "2") (pinfunction "S_2") (pintype "passive"))
    )
    (net (code "46") (name "/IICSDA") (class "Default")
      (node (ref "DD2") (pin "5") (pinfunction "SDA_5") (pintype "bidirectional"))
      (node (ref "SA1") (pin "JP2_47") (pinfunction "IICSDA_JP2_47") (pintype "bidirectional"))
      (node (ref "SA2") (pin "1") (pinfunction "S_1") (pintype "passive"))
    )
    (net (code "47") (name "/KIN0") (class "Default")
      (node (ref "CON1") (pin "1") (pinfunction "1_1") (pintype "bidirectional"))
      (node (ref "DA1") (pin "37") (pinfunction "KIN0_37") (pintype "input"))
      (node (ref "R14") (pin "1") (pinfunction "1_1") (pintype "passive"))
    )
    (net (code "48") (name "/KIN1") (class "Default")
      (node (ref "CON1") (pin "2") (pinfunction "2_2") (pintype "bidirectional"))
      (node (ref "DA1") (pin "36") (pinfunction "KIN1_36") (pintype "input"))
      (node (ref "RS7") (pin "1") (pinfunction "1_1") (pintype "passive"))
    )
    (net (code "49") (name "/KIN2") (class "Default")
      (node (ref "CON1") (pin "3") (pinfunction "3_3") (pintype "bidirectional"))
      (node (ref "DA1") (pin "35") (pinfunction "KIN2_35") (pintype "input"))
      (node (ref "RS7") (pin "2") (pinfunction "2_2") (pintype "passive"))
    )
    (net (code "50") (name "/KIN3") (class "Default")
      (node (ref "CON1") (pin "4") (pinfunction "4_4") (pintype "bidirectional"))
      (node (ref "DA1") (pin "34") (pinfunction "KIN3_34") (pintype "input"))
      (node (ref "RS7") (pin "3") (pinfunction "3_3") (pintype "passive"))
    )
    (net (code "51") (name "/KIN4") (class "Default")
      (node (ref "CON1") (pin "5") (pinfunction "5_5") (pintype "bidirectional"))
      (node (ref "DA1") (pin "33") (pinfunction "KIN4_33") (pintype "input"))
      (node (ref "RS7") (pin "4") (pinfunction "4_4") (pintype "passive"))
    )
    (net (code "52") (name "/KOUT0") (class "Default")
      (node (ref "CON1") (pin "6") (pinfunction "6_6") (pintype "bidirectional"))
      (node (ref "DA1") (pin "32") (pinfunction "KOUT0_32") (pintype "output"))
    )
    (net (code "53") (name "/KOUT1") (class "Default")
      (node (ref "CON1") (pin "7") (pinfunction "7_7") (pintype "bidirectional"))
      (node (ref "DA1") (pin "31") (pinfunction "KOUT1_31") (pintype "output"))
    )
    (net (code "54") (name "/KOUT2") (class "Default")
      (node (ref "CON1") (pin "8") (pinfunction "8_8") (pintype "bidirectional"))
      (node (ref "DA1") (pin "30") (pinfunction "KOUT2_30") (pintype "output"))
    )
    (net (code "55") (name "/KOUT3") (class "Default")
      (node (ref "CON1") (pin "9") (pinfunction "9_9") (pintype "bidirectional"))
      (node (ref "DA1") (pin "29") (pinfunction "KOUT3_29") (pintype "output"))
    )
    (net (code "56") (name "/MISO") (class "Default")
      (node (ref "CON2") (pin "9") (pinfunction "9_9") (pintype "bidirectional"))
      (node (ref "RS8") (pin "2") (pinfunction "2_2") (pintype "passive"))
      (node (ref "SA1") (pin "JP2_12") (pinfunction "PB6_JP2_12") (pintype "bidirectional"))
    )
    (net (code "57") (name "/MOSI") (class "Default")
      (node (ref "CON2") (pin "10") (pinfunction "10_10") (pintype "bidirectional"))
      (node (ref "RS8") (pin "3") (pinfunction "3_3") (pintype "passive"))
      (node (ref "SA1") (pin "JP2_11") (pinfunction "PB7_JP2_11") (pintype "bidirectional"))
    )
    (net (code "58") (name "/PA0") (class "Default")
      (node (ref "CON2") (pin "8") (pinfunction "8_8") (pintype "bidirectional"))
      (node (ref "SA1") (pin "JP2_8") (pinfunction "PA0_JP2_8") (pintype "bidirectional"))
    )
    (net (code "59") (name "/PA1") (class "Default")
      (node (ref "CON2") (pin "7") (pinfunction "7_7") (pintype "bidirectional"))
      (node (ref "SA1") (pin "JP2_7") (pinfunction "PA1_JP2_7") (pintype "bidirectional"))
    )
    (net (code "60") (name "/PA2") (class "Default")
      (node (ref "CON2") (pin "6") (pinfunction "6_6") (pintype "bidirectional"))
      (node (ref "SA1") (pin "JP2_6") (pinfunction "PA2_JP2_6") (pintype "bidirectional"))
    )
    (net (code "61") (name "/PA3") (class "Default")
      (node (ref "CON2") (pin "5") (pinfunction "5_5") (pintype "bidirectional"))
      (node (ref "SA1") (pin "JP2_5") (pinfunction "PA3_JP2_5") (pintype "bidirectional"))
    )
    (net (code "62") (name "/PA4") (class "Default")
      (node (ref "CON2") (pin "4") (pinfunction "4_4") (pintype "bidirectional"))
      (node (ref "SA1") (pin "JP2_4") (pinfunction "PA4_JP2_4") (pintype "bidirectional"))
    )
    (net (code "63") (name "/PA5") (class "Default")
      (node (ref "CON2") (pin "3") (pinfunction "3_3") (pintype "bidirectional"))
      (node (ref "SA1") (pin "JP2_3") (pinfunction "PA5_JP2_3") (pintype "bidirectional"))
    )
    (net (code "64") (name "/PA6") (class "Default")
      (node (ref "CON2") (pin "2") (pinfunction "2_2") (pintype "bidirectional"))
      (node (ref "SA1") (pin "JP2_2") (pinfunction "PA6_JP2_2") (pintype "bidirectional"))
    )
    (net (code "65") (name "/PA7") (class "Default")
      (node (ref "CON2") (pin "1") (pinfunction "1_1") (pintype "bidirectional"))
      (node (ref "SA1") (pin "JP2_1") (pinfunction "PA7_JP2_1") (pintype "bidirectional"))
    )
    (net (code "66") (name "/PB0") (class "Default")
      (node (ref "CON3") (pin "5") (pinfunction "5_5") (pintype "bidirectional"))
      (node (ref "SA1") (pin "JP2_18") (pinfunction "PB0_JP2_18") (pintype "bidirectional"))
    )
    (net (code "67") (name "/PB1") (class "Default")
      (node (ref "CON3") (pin "6") (pinfunction "6_6") (pintype "bidirectional"))
      (node (ref "SA1") (pin "JP2_17") (pinfunction "PB1_JP2_17") (pintype "bidirectional"))
    )
    (net (code "68") (name "/PB2") (class "Default")
      (node (ref "CON3") (pin "3") (pinfunction "3_3") (pintype "bidirectional"))
      (node (ref "R41") (pin "1") (pinfunction "1_1") (pintype "passive"))
      (node (ref "SA1") (pin "JP2_16") (pinfunction "PB2_JP2_16") (pintype "bidirectional"))
    )
    (net (code "69") (name "/PB4") (class "Default")
      (node (ref "CON3") (pin "1") (pinfunction "1_1") (pintype "bidirectional"))
      (node (ref "SA1") (pin "JP2_14") (pinfunction "PB4_JP2_14") (pintype "bidirectional"))
    )
    (net (code "70") (name "/PB5") (class "Default")
      (node (ref "CON3") (pin "2") (pinfunction "2_2") (pintype "bidirectional"))
      (node (ref "SA1") (pin "JP2_13") (pinfunction "PB5_JP2_13") (pintype "bidirectional"))
    )
    (net (code "71") (name "/PC0") (class "Default")
      (node (ref "CON4") (pin "5") (pinfunction "5_5") (pintype "bidirectional"))
      (node (ref "IC1") (pin "5") (pinfunction "RXD_5") (pintype "input"))
      (node (ref "SA1") (pin "JP2_27") (pinfunction "PC0_JP2_27") (pintype "bidirectional"))
    )
    (net (code "72") (name "/PC1") (class "Default")
      (node (ref "CON4") (pin "2") (pinfunction "2_2") (pintype "bidirectional"))
      (node (ref "IC1") (pin "1") (pinfunction "TXD_1") (pintype "output"))
      (node (ref "SA1") (pin "JP2_26") (pinfunction "PC1_JP2_26") (pintype "bidirectional"))
    )
    (net (code "73") (name "/PC2") (class "Default")
      (node (ref "CON4") (pin "3") (pinfunction "3_3") (pintype "bidirectional"))
      (node (ref "SA1") (pin "JP2_25") (pinfunction "PC2_JP2_25") (pintype "bidirectional"))
    )
    (net (code "74") (name "/PC3") (class "Default")
      (node (ref "CON3") (pin "10") (pinfunction "10_10") (pintype "bidirectional"))
      (node (ref "SA1") (pin "JP2_24") (pinfunction "PC3_JP2_24") (pintype "bidirectional"))
    )
    (net (code "75") (name "/PC4") (class "Default")
      (node (ref "CON4") (pin "1") (pinfunction "1_1") (pintype "bidirectional"))
      (node (ref "SA1") (pin "JP2_23") (pinfunction "PC4_JP2_23") (pintype "bidirectional"))
    )
    (net (code "76") (name "/PC5") (class "Default")
      (node (ref "CON3") (pin "8") (pinfunction "8_8") (pintype "bidirectional"))
      (node (ref "SA1") (pin "JP2_22") (pinfunction "PC5_JP2_22") (pintype "bidirectional"))
    )
    (net (code "77") (name "/PC6") (class "Default")
      (node (ref "CON3") (pin "9") (pinfunction "9_9") (pintype "bidirectional"))
      (node (ref "SA1") (pin "JP2_21") (pinfunction "PC6_JP2_21") (pintype "bidirectional"))
    )
    (net (code "78") (name "/PC7") (class "Default")
      (node (ref "CON3") (pin "7") (pinfunction "7_7") (pintype "bidirectional"))
      (node (ref "SA1") (pin "JP2_20") (pinfunction "PC7_JP2_20") (pintype "bidirectional"))
    )
    (net (code "79") (name "/PCLK") (class "Default")
      (node (ref "DA1") (pin "49") (pinfunction "PCLC_49") (pintype "output"))
      (node (ref "RS5") (pin "4") (pinfunction "4_4") (pintype "passive"))
    )
    (net (code "80") (name "/PD0") (class "Default")
      (node (ref "DD3") (pin "4") (pinfunction "DI_4") (pintype "input"))
      (node (ref "SA1") (pin "JP2_36") (pinfunction "PD0_JP2_36") (pintype "bidirectional"))
    )
    (net (code "81") (name "/PD1") (class "Default")
      (node (ref "DD3") (pin "1") (pinfunction "RO_1") (pintype "output"))
      (node (ref "R5") (pin "2") (pinfunction "2_2") (pintype "passive"))
      (node (ref "SA1") (pin "JP2_35") (pinfunction "PD1_JP2_35") (pintype "bidirectional"))
    )
    (net (code "82") (name "/PD2") (class "Default")
      (node (ref "CON4") (pin "9") (pinfunction "9_9") (pintype "bidirectional"))
      (node (ref "DD3") (pin "3") (pinfunction "DE_3") (pintype "input"))
      (node (ref "R4") (pin "1") (pinfunction "1_1") (pintype "passive"))
      (node (ref "SA1") (pin "JP2_34") (pinfunction "PD2_JP2_34") (pintype "bidirectional"))
    )
    (net (code "83") (name "/PD3") (class "Default")
      (node (ref "CON4") (pin "10") (pinfunction "10_10") (pintype "bidirectional"))
      (node (ref "R48") (pin "1") (pinfunction "1_1") (pintype "passive"))
      (node (ref "SA1") (pin "JP2_33") (pinfunction "PD3_JP2_33") (pintype "bidirectional"))
    )
    (net (code "84") (name "/PD4") (class "Default")
      (node (ref "CON4") (pin "7") (pinfunction "7_7") (pintype "bidirectional"))
      (node (ref "DA1") (pin "9") (pinfunction "~{RST}_9") (pintype "input"))
      (node (ref "R2") (pin "1") (pinfunction "1_1") (pintype "passive"))
      (node (ref "SA1") (pin "JP2_32") (pinfunction "PD4_JP2_32") (pintype "bidirectional"))
    )
    (net (code "85") (name "/PD5") (class "Default")
      (node (ref "CON4") (pin "8") (pinfunction "8_8") (pintype "bidirectional"))
      (node (ref "RS8") (pin "1") (pinfunction "1_1") (pintype "passive"))
      (node (ref "SA1") (pin "JP2_31") (pinfunction "PD5_JP2_31") (pintype "bidirectional"))
    )
    (net (code "86") (name "/PD6") (class "Default")
      (node (ref "CON4") (pin "6") (pinfunction "6_6") (pintype "bidirectional"))
      (node (ref "R61") (pin "1") (pinfunction "1_1") (pintype "passive"))
      (node (ref "SA1") (pin "JP2_29") (pinfunction "PD6_JP2_29") (pintype "bidirectional"))
    )
    (net (code "87") (name "/PD7") (class "Default")
      (node (ref "CON4") (pin "4") (pinfunction "4_4") (pintype "bidirectional"))
      (node (ref "SA1") (pin "JP2_28") (pinfunction "PD7_JP2_28") (pintype "bidirectional"))
    )
    (net (code "88") (name "/PDAT0") (class "Default")
      (node (ref "DA1") (pin "51") (pinfunction "PDAT0_51") (pintype "output"))
      (node (ref "RS2") (pin "4") (pinfunction "4_4") (pintype "passive"))
    )
    (net (code "89") (name "/PDAT1") (class "Default")
      (node (ref "DA1") (pin "52") (pinfunction "PDAT1_52") (pintype "output"))
      (node (ref "RS2") (pin "3") (pinfunction "3_3") (pintype "passive"))
    )
    (net (code "90") (name "/PDAT2") (class "Default")
      (node (ref "DA1") (pin "53") (pinfunction "PDAT2_53") (pintype "output"))
      (node (ref "RS2") (pin "2") (pinfunction "2_2") (pintype "passive"))
    )
    (net (code "91") (name "/PDAT3") (class "Default")
      (node (ref "DA1") (pin "54") (pinfunction "PDAT3_54") (pintype "output"))
      (node (ref "RS2") (pin "1") (pinfunction "1_1") (pintype "passive"))
    )
    (net (code "92") (name "/PDAT4") (class "Default")
      (node (ref "DA1") (pin "55") (pinfunction "PDAT4_55") (pintype "output"))
      (node (ref "RS1") (pin "4") (pinfunction "4_4") (pintype "passive"))
    )
    (net (code "93") (name "/PDAT5") (class "Default")
      (node (ref "DA1") (pin "56") (pinfunction "PDAT5_56") (pintype "output"))
      (node (ref "RS4") (pin "2") (pinfunction "2_2") (pintype "passive"))
    )
    (net (code "94") (name "/PDAT6") (class "Default")
      (node (ref "DA1") (pin "57") (pinfunction "PDAT6_57") (pintype "output"))
      (node (ref "RS4") (pin "1") (pinfunction "1_1") (pintype "passive"))
    )
    (net (code "95") (name "/PDAT7") (class "Default")
      (node (ref "DA1") (pin "58") (pinfunction "PDAT7_58") (pintype "output"))
      (node (ref "RS3") (pin "4") (pinfunction "4_4") (pintype "passive"))
    )
    (net (code "96") (name "/PDAT8") (class "Default")
      (node (ref "DA1") (pin "59") (pinfunction "PDAT8_59") (pintype "output"))
      (node (ref "RS3") (pin "3") (pinfunction "3_3") (pintype "passive"))
    )
    (net (code "97") (name "/PDAT9") (class "Default")
      (node (ref "DA1") (pin "63") (pinfunction "PDAT9_63") (pintype "output"))
      (node (ref "RS3") (pin "2") (pinfunction "2_2") (pintype "passive"))
    )
    (net (code "98") (name "/PDAT10") (class "Default")
      (node (ref "DA1") (pin "64") (pinfunction "PDAT10_64") (pintype "output"))
      (node (ref "RS3") (pin "1") (pinfunction "1_1") (pintype "passive"))
    )
    (net (code "99") (name "/PDAT11") (class "Default")
      (node (ref "DA1") (pin "65") (pinfunction "PDAT11_65") (pintype "output"))
      (node (ref "RS5") (pin "3") (pinfunction "3_3") (pintype "passive"))
    )
    (net (code "100") (name "/PDAT12") (class "Default")
      (node (ref "DA1") (pin "66") (pinfunction "PDAT12_66") (pintype "output"))
      (node (ref "RS5") (pin "2") (pinfunction "2_2") (pintype "passive"))
    )
    (net (code "101") (name "/PDAT13") (class "Default")
      (node (ref "DA1") (pin "67") (pinfunction "PDAT13_67") (pintype "output"))
      (node (ref "RS5") (pin "1") (pinfunction "1_1") (pintype "passive"))
    )
    (net (code "102") (name "/PDAT14") (class "Default")
      (node (ref "DA1") (pin "68") (pinfunction "PDAT14_68") (pintype "output"))
      (node (ref "RS4") (pin "4") (pinfunction "4_4") (pintype "passive"))
    )
    (net (code "103") (name "/PDAT15") (class "Default")
      (node (ref "DA1") (pin "69") (pinfunction "PDAT15_69") (pintype "output"))
      (node (ref "RS4") (pin "3") (pinfunction "3_3") (pintype "passive"))
    )
    (net (code "104") (name "/PS") (class "Default")
      (node (ref "DA1") (pin "25") (pinfunction "PS_25") (pintype "input"))
      (node (ref "R27") (pin "2") (pinfunction "2_2") (pintype "passive"))
      (node (ref "R28") (pin "1") (pinfunction "1_1") (pintype "passive"))
    )
    (net (code "105") (name "/PWM1") (class "Default")
      (node (ref "DA1") (pin "14") (pinfunction "PWM1_14") (pintype "output"))
      (node (ref "R53") (pin "2") (pinfunction "2_2") (pintype "passive"))
    )
    (net (code "106") (name "/PWM2") (class "Default")
      (node (ref "DA1") (pin "15") (pinfunction "PWM2_15") (pintype "output"))
    )
    (net (code "107") (name "/RESET") (class "Default")
      (node (ref "C25") (pin "1") (pinfunction "1_1") (pintype "passive"))
      (node (ref "J1") (pin "44") (pinfunction "MS_44") (pintype "passive"))
      (node (ref "R21") (pin "2") (pinfunction "2_2") (pintype "passive"))
    )
    (net (code "108") (name "/RS485_A") (class "Default")
      (node (ref "DD3") (pin "6") (pinfunction "A_6") (pintype "bidirectional"))
      (node (ref "R7") (pin "2") (pinfunction "2_2") (pintype "passive"))
      (node (ref "R8") (pin "1") (pinfunction "1_1") (pintype "passive"))
      (node (ref "X1") (pin "1") (pinfunction "K_1") (pintype "passive"))
    )
    (net (code "109") (name "/RS485_B") (class "Default")
      (node (ref "DD3") (pin "7") (pinfunction "B_7") (pintype "bidirectional"))
      (node (ref "R6") (pin "1") (pinfunction "1_1") (pintype "passive"))
      (node (ref "R8") (pin "2") (pinfunction "2_2") (pintype "passive"))
      (node (ref "X1") (pin "2") (pinfunction "K_2") (pintype "passive"))
    )
    (net (code "110") (name "/RTC_VDD") (class "Default")
      (node (ref "BAT1") (pin "+") (pinfunction "PLUS_+") (pintype "power_in"))
      (node (ref "SA1") (pin "JP2_43") (pinfunction "RTC_VDD_JP2_43") (pintype "power_in"))
    )
    (net (code "111") (name "/SCK") (class "Default")
      (node (ref "CON3") (pin "4") (pinfunction "4_4") (pintype "bidirectional"))
      (node (ref "RS8") (pin "4") (pinfunction "4_4") (pintype "passive"))
      (node (ref "SA1") (pin "JP2_15") (pinfunction "PB3_JP2_15") (pintype "bidirectional"))
    )
    (net (code "112") (name "/SCL") (class "Default")
      (node (ref "DA1") (pin "44") (pinfunction "SCL_44") (pintype "input"))
      (node (ref "RS8") (pin "5") (pinfunction "5_5") (pintype "passive"))
      (node (ref "RS9") (pin "8") (pinfunction "8_8") (pintype "passive"))
    )
    (net (code "113") (name "/SDI") (class "Default")
      (node (ref "DA1") (pin "43") (pinfunction "SDI_43") (pintype "bidirectional"))
      (node (ref "RS8") (pin "6") (pinfunction "6_6") (pintype "passive"))
      (node (ref "RS9") (pin "7") (pinfunction "7_7") (pintype "passive"))
    )
    (net (code "114") (name "/SDO") (class "Default")
      (node (ref "DA1") (pin "42") (pinfunction "SDO_42") (pintype "bidirectional"))
      (node (ref "RS8") (pin "7") (pinfunction "7_7") (pintype "passive"))
      (node (ref "RS9") (pin "6") (pinfunction "6_6") (pintype "passive"))
    )
    (net (code "115") (name "/SFCL") (class "Default")
      (node (ref "DA1") (pin "18") (pinfunction "SFCL_18") (pintype "output"))
      (node (ref "DD4") (pin "6") (pinfunction "CLK_6") (pintype "input"))
      (node (ref "DD5") (pin "6") (pinfunction "CLK_6") (pintype "input"))
      (node (ref "RS6") (pin "8") (pinfunction "8_8") (pintype "passive"))
      (node (ref "SA4") (pin "7") (pinfunction "7_7") (pintype "bidirectional"))
      (node (ref "SA5") (pin "7") (pinfunction "7_7") (pintype "bidirectional"))
    )
    (net (code "116") (name "/SFDI") (class "Default")
      (node (ref "DA1") (pin "19") (pinfunction "SFDI/SIO0_19") (pintype "bidirectional"))
      (node (ref "DD4") (pin "5") (pinfunction "MOSI_5") (pintype "bidirectional"))
      (node (ref "DD5") (pin "5") (pinfunction "MOSI_5") (pintype "bidirectional"))
      (node (ref "RS6") (pin "7") (pinfunction "7_7") (pintype "passive"))
      (node (ref "SA4") (pin "6") (pinfunction "6_6") (pintype "bidirectional"))
      (node (ref "SA5") (pin "6") (pinfunction "6_6") (pintype "bidirectional"))
    )
    (net (code "117") (name "/SFDO") (class "Default")
      (node (ref "DA1") (pin "20") (pinfunction "SFDO/SIO1_20") (pintype "bidirectional"))
      (node (ref "DD4") (pin "2") (pinfunction "MISO_2") (pintype "bidirectional"))
      (node (ref "DD5") (pin "2") (pinfunction "MISO_2") (pintype "bidirectional"))
      (node (ref "RS6") (pin "6") (pinfunction "6_6") (pintype "passive"))
      (node (ref "SA4") (pin "3") (pinfunction "3_3") (pintype "bidirectional"))
      (node (ref "SA5") (pin "3") (pinfunction "3_3") (pintype "bidirectional"))
    )
    (net (code "118") (name "/SIFS0") (class "Default")
      (node (ref "DA1") (pin "28") (pinfunction "SIFS0_28") (pintype "input"))
      (node (ref "R37") (pin "2") (pinfunction "2_2") (pintype "passive"))
      (node (ref "R38") (pin "1") (pinfunction "1_1") (pintype "passive"))
    )
    (net (code "119") (name "/SIFS1") (class "Default")
      (node (ref "DA1") (pin "27") (pinfunction "SIFS1_27") (pintype "input"))
      (node (ref "R39") (pin "2") (pinfunction "2_2") (pintype "passive"))
      (node (ref "R40") (pin "1") (pinfunction "1_1") (pintype "passive"))
    )
    (net (code "120") (name "/TCK") (class "Default")
      (node (ref "SA1") (pin "JP2_41") (pinfunction "TCK_JP2_41") (pintype "input"))
      (node (ref "SA3") (pin "4") (pinfunction "TCK_4") (pintype "bidirectional"))
    )
    (net (code "121") (name "/TDI") (class "Default")
      (node (ref "SA1") (pin "JP2_38") (pinfunction "TDI_JP2_38") (pintype "input"))
      (node (ref "SA3") (pin "6") (pinfunction "TDI_6") (pintype "bidirectional"))
    )
    (net (code "122") (name "/TDO") (class "Default")
      (node (ref "SA1") (pin "JP2_37") (pinfunction "TDO_JP2_37") (pintype "output"))
    )
    (net (code "123") (name "/TMS") (class "Default")
      (node (ref "SA1") (pin "JP2_42") (pinfunction "TMS_JP2_42") (pintype "input"))
    )
    (net (code "124") (name "/TRIGOUT") (class "Default")
      (node (ref "SA1") (pin "JP2_40") (pinfunction "TRIGOUT_JP2_40") (pintype "output"))
    )
    (net (code "125") (name "/USB_5V") (class "Default")
      (node (ref "C17") (pin "1") (pinfunction "1_1") (pintype "passive"))
      (node (ref "C19") (pin "1") (pinfunction "1_1") (pintype "passive"))
      (node (ref "IC1") (pin "20") (pinfunction "VCC_20") (pintype "power_in"))
      (node (ref "L1") (pin "2") (pinfunction "L2_2") (pintype "passive"))
      (node (ref "LED1") (pin "A") (pinfunction "A_A") (pintype "passive"))
      (node (ref "LED2") (pin "A") (pinfunction "A_A") (pintype "passive"))
      (node (ref "VD1") (pin "4") (pinfunction "VCC_4") (pintype "power_in"))
    )
    (net (code "126") (name "/VCOM") (class "Default")
      (node (ref "C37") (pin "1") (pinfunction "1_1") (pintype "passive"))
      (node (ref "C38") (pin "1") (pinfunction "1_1") (pintype "passive"))
      (node (ref "J1") (pin "46") (pinfunction "MS_46") (pintype "passive"))
      (node (ref "J1") (pin "6") (pinfunction "MS_6") (pintype "passive"))
      (node (ref "R54") (pin "2") (pinfunction "2_2") (pintype "passive"))
      (node (ref "R55") (pin "1") (pinfunction "1_1") (pintype "passive"))
    )
    (net (code "127") (name "/VGH") (class "Default")
      (node (ref "C22") (pin "1") (pinfunction "1_1") (pintype "passive"))
      (node (ref "C48") (pin "1") (pinfunction "1_1") (pintype "passive"))
      (node (ref "J1") (pin "41") (pinfunction "MS_41") (pintype "passive"))
      (node (ref "R17") (pin "1") (pinfunction "1_1") (pintype "passive"))
      (node (ref "R49") (pin "1") (pinfunction "1_1") (pintype "passive"))
      (node (ref "R57") (pin "1") (pinfunction "1_1") (pintype "passive"))
      (node (ref "VD2") (pin "C") (pinfunction "C_C") (pintype "passive"))
      (node (ref "VD3") (pin "C") (pinfunction "C_C") (pintype "passive"))
    )
    (net (code "128") (name "/VGL") (class "Default")
      (node (ref "C51") (pin "1") (pinfunction "1_1") (pintype "passive"))
      (node (ref "J1") (pin "42") (pinfunction "MS_42") (pintype "passive"))
      (node (ref "R20") (pin "1") (pinfunction "1_1") (pintype "passive"))
      (node (ref "VD6") (pin "C") (pinfunction "C_C") (pintype "passive"))
    )
    (net (code "129") (name "/VSYNC") (class "Default")
      (node (ref "DA1") (pin "48") (pinfunction "VSYNC_48") (pintype "output"))
      (node (ref "RS1") (pin "2") (pinfunction "2_2") (pintype "passive"))
    )
    (net (code "130") (name "/XN") (class "Default")
      (node (ref "C46") (pin "1") (pinfunction "1_1") (pintype "passive"))
      (node (ref "CN1") (pin "4") (pinfunction "4_4") (pintype "bidirectional"))
      (node (ref "DA1") (pin "72") (pinfunction "XN_72") (pintype "bidirectional"))
    )
    (net (code "131") (name "/XP") (class "Default")
      (node (ref "C44") (pin "1") (pinfunction "1_1") (pintype "passive"))
      (node (ref "CN1") (pin "2") (pinfunction "2_2") (pintype "bidirectional"))
      (node (ref "DA1") (pin "75") (pinfunction "XP_75") (pintype "bidirectional"))
    )
    (net (code "132") (name "/YN") (class "Default")
      (node (ref "C43") (pin "1") (pinfunction "1_1") (pintype "passive"))
      (node (ref "CN1") (pin "1") (pinfunction "1_1") (pintype "bidirectional"))
      (node (ref "DA1") (pin "74") (pinfunction "YN_74") (pintype "bidirectional"))
    )
    (net (code "133") (name "/YP") (class "Default")
      (node (ref "C45") (pin "1") (pinfunction "1_1") (pintype "passive"))
      (node (ref "CN1") (pin "3") (pinfunction "3_3") (pintype "bidirectional"))
      (node (ref "DA1") (pin "73") (pinfunction "YP_73") (pintype "bidirectional"))
      (node (ref "R62") (pin "2") (pinfunction "2_2") (pintype "passive"))
    )
    (net (code "134") (name "/~{BUSACK}") (class "Default")
      (node (ref "SA1") (pin "JP1_59") (pinfunction "~{BUSACK}_JP1_59") (pintype "output"))
    )
    (net (code "135") (name "/~{BUSREQ}") (class "Default")
      (node (ref "R12") (pin "1") (pinfunction "1_1") (pintype "passive"))
      (node (ref "SA1") (pin "JP1_60") (pinfunction "~{BUSREQ}_JP1_60") (pintype "input"))
    )
    (net (code "136") (name "/~{CS2}") (class "Default")
      (node (ref "DD1") (pin "8") (pinfunction "~{CE}_8") (pintype "input"))
      (node (ref "SA1") (pin "JP1_43") (pinfunction "~{CS2}_JP1_43") (pintype "output"))
    )
    (net (code "137") (name "/~{CS3}") (class "Default")
      (node (ref "DA1") (pin "79") (pinfunction "~{CS}_79") (pintype "input"))
      (node (ref "SA1") (pin "JP2_51") (pinfunction "~{CS3}_JP2_51") (pintype "output"))
    )
    (net (code "138") (name "/~{DIS_FLASH}") (class "Default")
      (node (ref "R3") (pin "1") (pinfunction "1_1") (pintype "passive"))
      (node (ref "SA1") (pin "JP1_36") (pinfunction "~{DIS_FLASH}_JP1_36") (pintype "input"))
    )
    (net (code "139") (name "/~{DIS_RDA}") (class "Default")
      (node (ref "R43") (pin "1") (pinfunction "1_1") (pintype "passive"))
      (node (ref "SA1") (pin "JP2_52") (pinfunction "~{DIS_IRDA}_JP2_52") (pintype "input"))
    )
    (net (code "140") (name "/~{F91_WE}") (class "Default")
      (node (ref "R44") (pin "2") (pinfunction "2_2") (pintype "passive"))
      (node (ref "SA1") (pin "JP1_7") (pinfunction "~{F91_WE}_JP1_7") (pintype "input"))
    )
    (net (code "141") (name "/~{FLASH_WE}") (class "Default")
      (node (ref "R42") (pin "2") (pinfunction "2_2") (pintype "passive"))
      (node (ref "SA1") (pin "JP2_49") (pinfunction "~{FLASH_WE}_JP2_49") (pintype "input"))
    )
    (net (code "142") (name "/~{HALT_SLP}") (class "Default")
      (node (ref "R11") (pin "2") (pinfunction "2_2") (pintype "passive"))
      (node (ref "SA1") (pin "JP2_57") (pinfunction "~{HALT_SLP}_JP2_57") (pintype "output"))
    )
    (net (code "143") (name "/~{INSTRD}") (class "Default")
      (node (ref "SA1") (pin "JP1_58") (pinfunction "~{INSTRD}_JP1_58") (pintype "output"))
    )
    (net (code "144") (name "/~{IORQ}") (class "Default")
      (node (ref "SA1") (pin "JP1_54") (pinfunction "~{IOREQ}_JP1_54") (pintype "bidirectional"))
    )
    (net (code "145") (name "/~{MREQ}") (class "Default")
      (node (ref "SA1") (pin "JP1_53") (pinfunction "~{MREQ1}_JP1_53") (pintype "bidirectional"))
    )
    (net (code "146") (name "/~{NMI}") (class "Default")
      (node (ref "R45") (pin "1") (pinfunction "1_1") (pintype "passive"))
      (node (ref "SA1") (pin "JP2_58") (pinfunction "~{NMI}_JP2_58") (pintype "input"))
    )
    (net (code "147") (name "/~{RD}") (class "Default")
      (node (ref "DA1") (pin "77") (pinfunction "~{RD}_77") (pintype "input"))
      (node (ref "DD1") (pin "37") (pinfunction "~{OE}_37") (pintype "input"))
      (node (ref "SA1") (pin "JP1_56") (pinfunction "~{RD}_JP1_56") (pintype "bidirectional"))
    )
    (net (code "148") (name "/~{RESET}") (class "Default")
      (node (ref "SA1") (pin "JP2_53") (pinfunction "~{RESET}_JP2_53") (pintype "bidirectional"))
      (node (ref "SA3") (pin "2") (pinfunction "RESET_2") (pintype "bidirectional"))
    )
    (net (code "149") (name "/~{SCS}") (class "Default")
      (node (ref "DA1") (pin "41") (pinfunction "~{SCS}_41") (pintype "input"))
      (node (ref "RS8") (pin "8") (pinfunction "8_8") (pintype "passive"))
      (node (ref "RS9") (pin "5") (pinfunction "5_5") (pintype "passive"))
    )
    (net (code "150") (name "/~{SFCS0}") (class "Default")
      (node (ref "DA1") (pin "21") (pinfunction "~{SFCS0}_21") (pintype "output"))
      (node (ref "DD4") (pin "1") (pinfunction "~{CS}_1") (pintype "input"))
      (node (ref "RS6") (pin "5") (pinfunction "5_5") (pintype "passive"))
      (node (ref "SA4") (pin "1") (pinfunction "1_1") (pintype "bidirectional"))
      (node (ref "SA5") (pin "1") (pinfunction "1_1") (pintype "bidirectional"))
    )
    (net (code "151") (name "/~{SFCS1}") (class "Default")
      (node (ref "DA1") (pin "22") (pinfunction "~{SFCS1}_22") (pintype "output"))
      (node (ref "DD5") (pin "1") (pinfunction "~{CS}_1") (pintype "input"))
      (node (ref "R13") (pin "2") (pinfunction "2_2") (pintype "passive"))
      (node (ref "SA4") (pin "2") (pinfunction "2_2") (pintype "bidirectional"))
      (node (ref "SA5") (pin "2") (pinfunction "2_2") (pintype "bidirectional"))
    )
    (net (code "152") (name "/~{SFWP}") (class "Default")
      (node (ref "DD4") (pin "3") (pinfunction "~{WP}_3") (pintype "input"))
      (node (ref "DD4") (pin "7") (pinfunction "~{HOLD}_7") (pintype "bidirectional"))
      (node (ref "DD5") (pin "3") (pinfunction "~{WP}_3") (pintype "input"))
      (node (ref "DD5") (pin "7") (pinfunction "~{HOLD}_7") (pintype "bidirectional"))
      (node (ref "R60") (pin "2") (pinfunction "2_2") (pintype "passive"))
      (node (ref "SA4") (pin "4") (pinfunction "4_4") (pintype "bidirectional"))
      (node (ref "SA4") (pin "8") (pinfunction "8_8") (pintype "bidirectional"))
      (node (ref "SA5") (pin "4") (pinfunction "4_4") (pintype "bidirectional"))
      (node (ref "SA5") (pin "8") (pinfunction "8_8") (pintype "bidirectional"))
    )
    (net (code "153") (name "/~{TRSTN}") (class "Default")
      (node (ref "SA1") (pin "JP1_5") (pinfunction "~{TRSTN}_JP1_5") (pintype "input"))
    )
    (net (code "154") (name "/~{WAIT}") (class "Default")
      (node (ref "SA1") (pin "JP2_54") (pinfunction "~{WAIT}_JP2_54") (pintype "input"))
    )
    (net (code "155") (name "/~{WR}") (class "Default")
      (node (ref "DA1") (pin "78") (pinfunction "~{WR}_78") (pintype "input"))
      (node (ref "DD1") (pin "15") (pinfunction "~{WE}_15") (pintype "input"))
      (node (ref "SA1") (pin "JP1_57") (pinfunction "~{WR}_JP1_57") (pintype "bidirectional"))
    )
    (net (code "156") (name "GND") (class "Default")
      (node (ref "BAT1") (pin "-") (pinfunction "MINUS_-") (pintype "power_in"))
      (node (ref "C1") (pin "2") (pinfunction "2_2") (pintype "passive"))
      (node (ref "C10") (pin "2") (pinfunction "2_2") (pintype "passive"))
      (node (ref "C11") (pin "2") (pinfunction "2_2") (pintype "passive"))
      (node (ref "C12") (pin "2") (pinfunction "2_2") (pintype "passive"))
      (node (ref "C13") (pin "2") (pinfunction "2_2") (pintype "passive"))
      (node (ref "C14") (pin "2") (pinfunction "2_2") (pintype "passive"))
      (node (ref "C15") (pin "2") (pinfunction "2_2") (pintype "passive"))
      (node (ref "C16") (pin "2") (pinfunction "2_2") (pintype "passive"))
      (node (ref "C17") (pin "2") (pinfunction "2_2") (pintype "passive"))
      (node (ref "C18") (pin "1") (pinfunction "1_1") (pintype "passive"))
      (node (ref "C19") (pin "2") (pinfunction "2_2") (pintype "passive"))
      (node (ref "C2") (pin "2") (pinfunction "2_2") (pintype "passive"))
      (node (ref "C20") (pin "2") (pinfunction "2_2") (pintype "passive"))
      (node (ref "C21") (pin "2") (pinfunction "2_2") (pintype "passive"))
      (node (ref "C22") (pin "2") (pinfunction "2_2") (pintype "passive"))
      (node (ref "C24") (pin "2") (pinfunction "2_2") (pintype "passive"))
      (node (ref "C25") (pin "2") (pinfunction "2_2") (pintype "passive"))
      (node (ref "C26") (pin "2") (pinfunction "2_2") (pintype "passive"))
      (node (ref "C27") (pin "2") (pinfunction "2_2") (pintype "passive"))
      (node (ref "C28") (pin "-") (pinfunction "-_-") (pintype "passive"))
      (node (ref "C29") (pin "2") (pinfunction "2_2") (pintype "passive"))
      (node (ref "C3") (pin "2") (pinfunction "2_2") (pintype "passive"))
      (node (ref "C31") (pin "2") (pinfunction "2_2") (pintype "passive"))
      (node (ref "C32") (pin "2") (pinfunction "2_2") (pintype "passive"))
      (node (ref "C33") (pin "2") (pinfunction "2_2") (pintype "passive"))
      (node (ref "C34") (pin "2") (pinfunction "2_2") (pintype "passive"))
      (node (ref "C36") (pin "2") (pinfunction "2_2") (pintype "passive"))
      (node (ref "C37") (pin "2") (pinfunction "2_2") (pintype "passive"))
      (node (ref "C38") (pin "2") (pinfunction "2_2") (pintype "passive"))
      (node (ref "C39") (pin "2") (pinfunction "2_2") (pintype "passive"))
      (node (ref "C4") (pin "2") (pinfunction "2_2") (pintype "passive"))
      (node (ref "C40") (pin "2") (pinfunction "2_2") (pintype "passive"))
      (node (ref "C41") (pin "2") (pinfunction "2_2") (pintype "passive"))
      (node (ref "C42") (pin "2") (pinfunction "2_2") (pintype "passive"))
      (node (ref "C43") (pin "2") (pinfunction "2_2") (pintype "passive"))
      (node (ref "C44") (pin "2") (pinfunction "2_2") (pintype "passive"))
      (node (ref "C45") (pin "2") (pinfunction "2_2") (pintype "passive"))
      (node (ref "C46") (pin "2") (pinfunction "2_2") (pintype "passive"))
      (node (ref "C47") (pin "-") (pinfunction "-_-") (pintype "passive"))
      (node (ref "C48") (pin "2") (pinfunction "2_2") (pintype "passive"))
      (node (ref "C5") (pin "2") (pinfunction "2_2") (pintype "passive"))
      (node (ref "C50") (pin "2") (pinfunction "2_2") (pintype "passive"))
      (node (ref "C51") (pin "2") (pinfunction "2_2") (pintype "passive"))
      (node (ref "C52") (pin "2") (pinfunction "2_2") (pintype "passive"))
      (node (ref "C6") (pin "2") (pinfunction "2_2") (pintype "passive"))
      (node (ref "C7") (pin "2") (pinfunction "2_2") (pintype "passive"))
      (node (ref "C8") (pin "2") (pinfunction "2_2") (pintype "passive"))
      (node (ref "C9") (pin "2") (pinfunction "2_2") (pintype "passive"))
      (node (ref "CON1") (pin "10") (pinfunction "10_10") (pintype "bidirectional"))
      (node (ref "DA1") (pin "1") (pinfunction "OSC_GNDP_1") (pintype "power_in"))
      (node (ref "DA1") (pin "10") (pinfunction "TEST0_10") (pintype "input"))
      (node (ref "DA1") (pin "100") (pinfunction "DB15_100") (pintype "bidirectional"))
      (node (ref "DA1") (pin "11") (pinfunction "TEST1_11") (pintype "input"))
      (node (ref "DA1") (pin "12") (pinfunction "TEST2_12") (pintype "input"))
      (node (ref "DA1") (pin "16") (pinfunction "GND_16") (pintype "power_in"))
      (node (ref "DA1") (pin "23") (pinfunction "IICA0_23") (pintype "input"))
      (node (ref "DA1") (pin "24") (pinfunction "IICA1_24") (pintype "input"))
      (node (ref "DA1") (pin "26") (pinfunction "GND1_26") (pintype "power_in"))
      (node (ref "DA1") (pin "39") (pinfunction "GND2_39") (pintype "power_in"))
      (node (ref "DA1") (pin "6") (pinfunction "OSC_GND_6") (pintype "power_in"))
      (node (ref "DA1") (pin "61") (pinfunction "LDO_GND_61") (pintype "power_in"))
      (node (ref "DA1") (pin "70") (pinfunction "ADC_GND_70") (pintype "power_in"))
      (node (ref "DA1") (pin "85") (pinfunction "GND3_85") (pintype "power_in"))
      (node (ref "DA1") (pin "93") (pinfunction "DB8_93") (pintype "bidirectional"))
      (node (ref "DA1") (pin "94") (pinfunction "DB9_94") (pintype "bidirectional"))
      (node (ref "DA1") (pin "95") (pinfunction "DB10_95") (pintype "bidirectional"))
      (node (ref "DA1") (pin "96") (pinfunction "DB11_96") (pintype "bidirectional"))
      (node (ref "DA1") (pin "97") (pinfunction "DB12_97") (pintype "bidirectional"))
      (node (ref "DA1") (pin "98") (pinfunction "DB13_98") (pintype "bidirectional"))
      (node (ref "DA1") (pin "99") (pinfunction "DB14_99") (pintype "bidirectional"))
      (node (ref "DA2") (pin "2") (pinfunction "GND_2") (pintype "power_in"))
      (node (ref "DA3") (pin "3") (pinfunction "GND_3") (pintype "power_in"))
      (node (ref "DA3") (pin "6") (pinfunction "GND_6") (pintype "power_in"))
      (node (ref "DA4") (pin "2") (pinfunction "GND_2") (pintype "power_in"))
      (node (ref "DD1") (pin "12") (pinfunction "GND_12") (pintype "power_in"))
      (node (ref "DD1") (pin "34") (pinfunction "GND1_34") (pintype "power_in"))
      (node (ref "DD2") (pin "2") (pinfunction "E1_2") (pintype "input"))
      (node (ref "DD2") (pin "3") (pinfunction "E2_3") (pintype "input"))
      (node (ref "DD2") (pin "4") (pinfunction "GND_4") (pintype "power_in"))
      (node (ref "DD2") (pin "7") (pinfunction "~{WC}_7") (pintype "input"))
      (node (ref "DD3") (pin "5") (pinfunction "VSS_5") (pintype "power_in"))
      (node (ref "DD4") (pin "4") (pinfunction "VSS_4") (pintype "power_in"))
      (node (ref "DD5") (pin "4") (pinfunction "VSS_4") (pintype "power_in"))
      (node (ref "IC1") (pin "18") (pinfunction "GND_18") (pintype "power_in"))
      (node (ref "IC1") (pin "21") (pinfunction "GND_21") (pintype "power_in"))
      (node (ref "IC1") (pin "25") (pinfunction "GND_25") (pintype "power_in"))
      (node (ref "IC1") (pin "26") (pinfunction "TEST_26") (pintype "input"))
      (node (ref "IC1") (pin "7") (pinfunction "GND_7") (pintype "power_in"))
      (node (ref "J1") (pin "17") (pinfunction "MS_17") (pintype "passive"))
      (node (ref "J1") (pin "18") (pinfunction "MS_18") (pintype "passive"))
      (node (ref "J1") (pin "19") (pinfunction "MS_19") (pintype "passive"))
      (node (ref "J1") (pin "26") (pinfunction "MS_26") (pintype "passive"))
      (node (ref "J1") (pin "27") (pinfunction "MS_27") (pintype "passive"))
      (node (ref "J1") (pin "33") (pinfunction "MS_33") (pintype "passive"))
      (node (ref "J1") (pin "34") (pinfunction "MS_34") (pintype "passive"))
      (node (ref "J1") (pin "35") (pinfunction "MS_35") (pintype "passive"))
      (node (ref "J1") (pin "36") (pinfunction "MS_36") (pintype "passive"))
      (node (ref "J1") (pin "38") (pinfunction "MS_38") (pintype "passive"))
      (node (ref "J1") (pin "48") (pinfunction "MS_48") (pintype "passive"))
      (node (ref "J1") (pin "5") (pinfunction "MS_5") (pintype "passive"))
      (node (ref "R10") (pin "2") (pinfunction "2_2") (pintype "passive"))
      (node (ref "R18") (pin "2") (pinfunction "2_2") (pintype "passive"))
      (node (ref "R19") (pin "2") (pinfunction "2_2") (pintype "passive"))
      (node (ref "R20") (pin "2") (pinfunction "2_2") (pintype "passive"))
      (node (ref "R23") (pin "2") (pinfunction "2_2") (pintype "passive"))
      (node (ref "R26") (pin "2") (pinfunction "2_2") (pintype "passive"))
      (node (ref "R28") (pin "2") (pinfunction "2_2") (pintype "passive"))
      (node (ref "R3") (pin "2") (pinfunction "2_2") (pintype "passive"))
      (node (ref "R30") (pin "2") (pinfunction "2_2") (pintype "passive"))
      (node (ref "R32") (pin "2") (pinfunction "2_2") (pintype "passive"))
      (node (ref "R34") (pin "2") (pinfunction "2_2") (pintype "passive"))
      (node (ref "R36") (pin "2") (pinfunction "2_2") (pintype "passive"))
      (node (ref "R38") (pin "2") (pinfunction "2_2") (pintype "passive"))
      (node (ref "R4") (pin "2") (pinfunction "2_2") (pintype "passive"))
      (node (ref "R40") (pin "2") (pinfunction "2_2") (pintype "passive"))
      (node (ref "R41") (pin "2") (pinfunction "2_2") (pintype "passive"))
      (node (ref "R42") (pin "1") (pinfunction "1_1") (pintype "passive"))
      (node (ref "R43") (pin "2") (pinfunction "2_2") (pintype "passive"))
      (node (ref "R44") (pin "1") (pinfunction "1_1") (pintype "passive"))
      (node (ref "R46") (pin "2") (pinfunction "2_2") (pintype "passive"))
      (node (ref "R47") (pin "2") (pinfunction "2_2") (pintype "passive"))
      (node (ref "R49") (pin "2") (pinfunction "2_2") (pintype "passive"))
      (node (ref "R50") (pin "2") (pinfunction "2_2") (pintype "passive"))
      (node (ref "R55") (pin "2") (pinfunction "2_2") (pintype "passive"))
      (node (ref "R56") (pin "2") (pinfunction "2_2") (pintype "passive"))
      (node (ref "R57") (pin "2") (pinfunction "2_2") (pintype "passive"))
      (node (ref "R59") (pin "2") (pinfunction "2_2") (pintype "passive"))
      (node (ref "R6") (pin "2") (pinfunction "2_2") (pintype "passive"))
      (node (ref "SA1") (pin "JP1_15") (pinfunction "GND2_JP1_15") (pintype "power_in"))
      (node (ref "SA1") (pin "JP1_26") (pinfunction "GND3_JP1_26") (pintype "power_in"))
      (node (ref "SA1") (pin "JP1_50") (pinfunction "GND4_JP1_50") (pintype "power_in"))
      (node (ref "SA1") (pin "JP1_55") (pinfunction "GND5_JP1_55") (pintype "power_in"))
      (node (ref "SA1") (pin "JP1_9") (pinfunction "GND1_JP1_9") (pintype "power_in"))
      (node (ref "SA1") (pin "JP2_10") (pinfunction "GND6_JP2_10") (pintype "power_in"))
      (node (ref "SA1") (pin "JP2_19") (pinfunction "GND8_JP2_19") (pintype "power_in"))
      (node (ref "SA1") (pin "JP2_30") (pinfunction "GND7_JP2_30") (pintype "power_in"))
      (node (ref "SA1") (pin "JP2_39") (pinfunction "GND9_JP2_39") (pintype "power_in"))
      (node (ref "SA1") (pin "JP2_46") (pinfunction "GND13_JP2_46") (pintype "power_in"))
      (node (ref "SA1") (pin "JP2_48") (pinfunction "GND12_JP2_48") (pintype "power_in"))
      (node (ref "SA1") (pin "JP2_50") (pinfunction "GND11_JP2_50") (pintype "power_in"))
      (node (ref "SA1") (pin "JP2_56") (pinfunction "GND10_JP2_56") (pintype "power_in"))
      (node (ref "SA2") (pin "3") (pinfunction "S_3") (pintype "passive"))
      (node (ref "SA3") (pin "3") (pinfunction "GND_3") (pintype "power_in"))
      (node (ref "SA3") (pin "5") (pinfunction "GND1_5") (pintype "power_in"))
      (node (ref "SA4") (pin "5") (pinfunction "5_5") (pintype "bidirectional"))
      (node (ref "SA5") (pin "5") (pinfunction "5_5") (pintype "bidirectional"))
      (node (ref "U$3") (pin "GND") (pinfunction "GND_GND") (pintype "bidirectional"))
      (node (ref "U$4") (pin "P$1") (pinfunction "S_P$1") (pintype "passive"))
      (node (ref "U$5") (pin "P$1") (pinfunction "S_P$1") (pintype "passive"))
      (node (ref "U$6") (pin "P$1") (pinfunction "S_P$1") (pintype "passive"))
      (node (ref "VD1") (pin "1") (pinfunction "GND_1") (pintype "power_in"))
      (node (ref "VD5") (pin "C") (pinfunction "C_C") (pintype "passive"))
      (node (ref "VT1") (pin "1") (pinfunction "G_1") (pintype "passive"))
      (node (ref "X1") (pin "3") (pinfunction "K_3") (pintype "passive"))
      (node (ref "X2") (pin "1") (pinfunction "K_1") (pintype "passive"))
    )
    (net (code "157") (name "Net-(C23-Pad1)") (class "Default")
      (node (ref "C23") (pin "1") (pinfunction "1_1") (pintype "passive"))
      (node (ref "VD4") (pin "C") (pinfunction "C_C") (pintype "passive"))
      (node (ref "VD5") (pin "A") (pinfunction "A_A") (pintype "passive"))
    )
    (net (code "158") (name "Net-(C24-Pad1)") (class "Default")
      (node (ref "C24") (pin "1") (pinfunction "1_1") (pintype "passive"))
      (node (ref "VD4") (pin "A") (pinfunction "A_A") (pintype "passive"))
      (node (ref "VD6") (pin "A") (pinfunction "A_A") (pintype "passive"))
    )
    (net (code "159") (name "Net-(C36-Pad1)") (class "Default")
      (node (ref "C36") (pin "1") (pinfunction "1_1") (pintype "passive"))
      (node (ref "R52") (pin "2") (pinfunction "2_2") (pintype "passive"))
      (node (ref "R53") (pin "1") (pinfunction "1_1") (pintype "passive"))
    )
    (net (code "160") (name "Net-(DA1-ADC_VREF)") (class "Default")
      (node (ref "C6") (pin "1") (pinfunction "1_1") (pintype "passive"))
      (node (ref "DA1") (pin "71") (pinfunction "ADC_VREF_71") (pintype "bidirectional"))
      (node (ref "R23") (pin "1") (pinfunction "1_1") (pintype "passive"))
      (node (ref "R24") (pin "2") (pinfunction "2_2") (pintype "passive"))
    )
    (net (code "161") (name "Net-(DA1-DE)") (class "Default")
      (node (ref "DA1") (pin "50") (pinfunction "DE_50") (pintype "output"))
      (node (ref "R58") (pin "2") (pinfunction "2_2") (pintype "passive"))
    )
    (net (code "162") (name "Net-(DA1-OSC_VDD)") (class "Default")
      (node (ref "C9") (pin "1") (pinfunction "1_1") (pintype "passive"))
      (node (ref "DA1") (pin "5") (pinfunction "OSC_VDD_5") (pintype "power_in"))
    )
    (net (code "163") (name "Net-(DA1-XI)") (class "Default")
      (node (ref "C8") (pin "1") (pinfunction "1_1") (pintype "passive"))
      (node (ref "DA1") (pin "3") (pinfunction "XI_3") (pintype "input"))
      (node (ref "Q1") (pin "1") (pinfunction "1_1") (pintype "passive"))
      (node (ref "R1") (pin "1") (pinfunction "1_1") (pintype "passive"))
    )
    (net (code "164") (name "Net-(DA1-XO)") (class "Default")
      (node (ref "C7") (pin "1") (pinfunction "1_1") (pintype "passive"))
      (node (ref "DA1") (pin "4") (pinfunction "XO_4") (pintype "output"))
      (node (ref "Q1") (pin "2") (pinfunction "2_2") (pintype "passive"))
      (node (ref "R1") (pin "2") (pinfunction "2_2") (pintype "passive"))
    )
    (net (code "165") (name "Net-(DA1-~{INT})") (class "Default")
      (node (ref "DA1") (pin "8") (pinfunction "~{INT}_8") (pintype "output"))
      (node (ref "R48") (pin "2") (pinfunction "2_2") (pintype "passive"))
    )
    (net (code "166") (name "Net-(DA1-~{WAIT})") (class "Default")
      (node (ref "DA1") (pin "7") (pinfunction "~{WAIT}_7") (pintype "output"))
      (node (ref "R61") (pin "2") (pinfunction "2_2") (pintype "passive"))
    )
    (net (code "167") (name "Net-(DA2-FB)") (class "Default")
      (node (ref "DA2") (pin "3") (pinfunction "FB_3") (pintype "input"))
      (node (ref "R17") (pin "2") (pinfunction "2_2") (pintype "passive"))
      (node (ref "R18") (pin "1") (pinfunction "1_1") (pintype "passive"))
    )
    (net (code "168") (name "Net-(DA2-SW)") (class "Default")
      (node (ref "C23") (pin "2") (pinfunction "2_2") (pintype "passive"))
      (node (ref "DA2") (pin "1") (pinfunction "SW_1") (pintype "output"))
      (node (ref "L2") (pin "P$2") (pinfunction "L2_P$2") (pintype "passive"))
      (node (ref "VD2") (pin "A") (pinfunction "A_A") (pintype "passive"))
    )
    (net (code "169") (name "Net-(DA3-REF)") (class "Default")
      (node (ref "DA3") (pin "5") (pinfunction "REF_5") (pintype "input"))
      (node (ref "R22") (pin "2") (pinfunction "2_2") (pintype "passive"))
      (node (ref "R46") (pin "1") (pinfunction "1_1") (pintype "passive"))
    )
    (net (code "170") (name "Net-(DA4-DRIVE)") (class "Default")
      (node (ref "DA4") (pin "6") (pinfunction "DRIVE_6") (pintype "output"))
      (node (ref "VT2") (pin "B") (pinfunction "B_B") (pintype "passive"))
    )
    (net (code "171") (name "Net-(DA4-SENCE)") (class "Default")
      (node (ref "DA4") (pin "4") (pinfunction "SENCE_4") (pintype "input"))
      (node (ref "R47") (pin "1") (pinfunction "1_1") (pintype "passive"))
      (node (ref "VT2") (pin "E") (pinfunction "E_E") (pintype "passive"))
    )
    (net (code "172") (name "Net-(DA4-VFB)") (class "Default")
      (node (ref "DA4") (pin "5") (pinfunction "VFB_5") (pintype "input"))
      (node (ref "R51") (pin "1") (pinfunction "1_1") (pintype "passive"))
      (node (ref "R52") (pin "1") (pinfunction "1_1") (pintype "passive"))
      (node (ref "VD8") (pin "A") (pinfunction "A_A") (pintype "passive"))
    )
    (net (code "173") (name "Net-(DD3-~{RE})") (class "Default")
      (node (ref "DD3") (pin "2") (pinfunction "~{RE}_2") (pintype "input"))
      (node (ref "R10") (pin "1") (pinfunction "1_1") (pintype "passive"))
      (node (ref "R9") (pin "2") (pinfunction "2_2") (pintype "passive"))
    )
    (net (code "174") (name "Net-(IC1-3V3OUT)") (class "Default")
      (node (ref "C18") (pin "2") (pinfunction "2_2") (pintype "passive"))
      (node (ref "IC1") (pin "17") (pinfunction "3V3OUT_17") (pintype "output"))
      (node (ref "IC1") (pin "4") (pinfunction "VCCIO_4") (pintype "power_in"))
    )
    (net (code "175") (name "Net-(IC1-CBUS0)") (class "Default")
      (node (ref "IC1") (pin "23") (pinfunction "CBUS0_23") (pintype "bidirectional"))
      (node (ref "R15") (pin "1") (pinfunction "1_1") (pintype "passive"))
    )
    (net (code "176") (name "Net-(IC1-CBUS1)") (class "Default")
      (node (ref "IC1") (pin "22") (pinfunction "CBUS1_22") (pintype "bidirectional"))
      (node (ref "R16") (pin "1") (pinfunction "1_1") (pintype "passive"))
    )
    (net (code "177") (name "Net-(IC1-USBDM)") (class "Default")
      (node (ref "IC1") (pin "16") (pinfunction "USBDM_16") (pintype "bidirectional"))
      (node (ref "U$3") (pin "D-") (pinfunction "D-_D-") (pintype "bidirectional"))
      (node (ref "VD1") (pin "2") (pinfunction "IO1_2") (pintype "bidirectional"))
    )
    (net (code "178") (name "Net-(IC1-USBDP)") (class "Default")
      (node (ref "IC1") (pin "15") (pinfunction "USBDP_15") (pintype "bidirectional"))
      (node (ref "U$3") (pin "D+") (pinfunction "D+_D+") (pintype "bidirectional"))
      (node (ref "VD1") (pin "3") (pinfunction "IO2_3") (pintype "bidirectional"))
    )
    (net (code "179") (name "Net-(J1AE-MS)") (class "Default")
      (node (ref "J1") (pin "37") (pinfunction "MS_37") (pintype "passive"))
      (node (ref "RS5") (pin "5") (pinfunction "5_5") (pintype "passive"))
    )
    (net (code "180") (name "Net-(J1AG-MS)") (class "Default")
      (node (ref "J1") (pin "39") (pinfunction "MS_39") (pintype "passive"))
      (node (ref "R29") (pin "2") (pinfunction "2_2") (pintype "passive"))
      (node (ref "R30") (pin "1") (pinfunction "1_1") (pintype "passive"))
    )
    (net (code "181") (name "Net-(J1AI-MS)") (class "Default")
      (node (ref "J1") (pin "40") (pinfunction "MS_40") (pintype "passive"))
      (node (ref "R31") (pin "2") (pinfunction "2_2") (pintype "passive"))
      (node (ref "R32") (pin "1") (pinfunction "1_1") (pintype "passive"))
    )
    (net (code "182") (name "Net-(J1AP-MS)") (class "Default")
      (node (ref "J1") (pin "47") (pinfunction "MS_47") (pintype "passive"))
      (node (ref "R35") (pin "2") (pinfunction "2_2") (pintype "passive"))
      (node (ref "R36") (pin "1") (pinfunction "1_1") (pintype "passive"))
    )
    (net (code "183") (name "Net-(J1AW-MS)") (class "Default")
      (node (ref "J1") (pin "8") (pinfunction "MS_8") (pintype "passive"))
      (node (ref "R33") (pin "2") (pinfunction "2_2") (pintype "passive"))
      (node (ref "R34") (pin "1") (pinfunction "1_1") (pintype "passive"))
    )
    (net (code "184") (name "Net-(J1AX-MS)") (class "Default")
      (node (ref "J1") (pin "9") (pinfunction "MS_9") (pintype "passive"))
      (node (ref "RS1") (pin "8") (pinfunction "8_8") (pintype "passive"))
    )
    (net (code "185") (name "Net-(J1B-MS)") (class "Default")
      (node (ref "J1") (pin "10") (pinfunction "MS_10") (pintype "passive"))
      (node (ref "RS1") (pin "7") (pinfunction "7_7") (pintype "passive"))
    )
    (net (code "186") (name "Net-(J1C-MS)") (class "Default")
      (node (ref "J1") (pin "11") (pinfunction "MS_11") (pintype "passive"))
      (node (ref "RS1") (pin "6") (pinfunction "6_6") (pintype "passive"))
    )
    (net (code "187") (name "Net-(J1D-MS)") (class "Default")
      (node (ref "J1") (pin "12") (pinfunction "MS_12") (pintype "passive"))
      (node (ref "RS1") (pin "5") (pinfunction "5_5") (pintype "passive"))
    )
    (net (code "188") (name "Net-(J1E-MS)") (class "Default")
      (node (ref "J1") (pin "13") (pinfunction "MS_13") (pintype "passive"))
      (node (ref "RS2") (pin "8") (pinfunction "8_8") (pintype "passive"))
    )
    (net (code "189") (name "Net-(J1F-MS)") (class "Default")
      (node (ref "J1") (pin "14") (pinfunction "MS_14") (pintype "passive"))
      (node (ref "RS2") (pin "7") (pinfunction "7_7") (pintype "passive"))
    )
    (net (code "190") (name "Net-(J1G-MS)") (class "Default")
      (node (ref "J1") (pin "15") (pinfunction "MS_15") (pintype "passive"))
      (node (ref "RS2") (pin "6") (pinfunction "6_6") (pintype "passive"))
    )
    (net (code "191") (name "Net-(J1H-MS)") (class "Default")
      (node (ref "J1") (pin "16") (pinfunction "MS_16") (pintype "passive"))
      (node (ref "RS2") (pin "5") (pinfunction "5_5") (pintype "passive"))
    )
    (net (code "192") (name "Net-(J1M-MS)") (class "Default")
      (node (ref "J1") (pin "20") (pinfunction "MS_20") (pintype "passive"))
      (node (ref "RS3") (pin "8") (pinfunction "8_8") (pintype "passive"))
    )
    (net (code "193") (name "Net-(J1N-MS)") (class "Default")
      (node (ref "J1") (pin "21") (pinfunction "MS_21") (pintype "passive"))
      (node (ref "RS3") (pin "7") (pinfunction "7_7") (pintype "passive"))
    )
    (net (code "194") (name "Net-(J1O-MS)") (class "Default")
      (node (ref "J1") (pin "22") (pinfunction "MS_22") (pintype "passive"))
      (node (ref "RS3") (pin "6") (pinfunction "6_6") (pintype "passive"))
    )
    (net (code "195") (name "Net-(J1P-MS)") (class "Default")
      (node (ref "J1") (pin "23") (pinfunction "MS_23") (pintype "passive"))
      (node (ref "RS3") (pin "5") (pinfunction "5_5") (pintype "passive"))
    )
    (net (code "196") (name "Net-(J1Q-MS)") (class "Default")
      (node (ref "J1") (pin "24") (pinfunction "MS_24") (pintype "passive"))
      (node (ref "RS4") (pin "8") (pinfunction "8_8") (pintype "passive"))
    )
    (net (code "197") (name "Net-(J1R-MS)") (class "Default")
      (node (ref "J1") (pin "25") (pinfunction "MS_25") (pintype "passive"))
      (node (ref "RS4") (pin "7") (pinfunction "7_7") (pintype "passive"))
    )
    (net (code "198") (name "Net-(J1U-MS)") (class "Default")
      (node (ref "J1") (pin "28") (pinfunction "MS_28") (pintype "passive"))
      (node (ref "RS4") (pin "6") (pinfunction "6_6") (pintype "passive"))
    )
    (net (code "199") (name "Net-(J1V-MS)") (class "Default")
      (node (ref "J1") (pin "29") (pinfunction "MS_29") (pintype "passive"))
      (node (ref "RS4") (pin "5") (pinfunction "5_5") (pintype "passive"))
    )
    (net (code "200") (name "Net-(J1X-MS)") (class "Default")
      (node (ref "J1") (pin "30") (pinfunction "MS_30") (pintype "passive"))
      (node (ref "RS5") (pin "8") (pinfunction "8_8") (pintype "passive"))
    )
    (net (code "201") (name "Net-(J1Y-MS)") (class "Default")
      (node (ref "J1") (pin "31") (pinfunction "MS_31") (pintype "passive"))
      (node (ref "RS5") (pin "7") (pinfunction "7_7") (pintype "passive"))
    )
    (net (code "202") (name "Net-(J1Z-MS)") (class "Default")
      (node (ref "J1") (pin "32") (pinfunction "MS_32") (pintype "passive"))
      (node (ref "RS5") (pin "6") (pinfunction "6_6") (pintype "passive"))
    )
    (net (code "203") (name "Net-(L1-L1)") (class "Default")
      (node (ref "L1") (pin "1") (pinfunction "L1_1") (pintype "passive"))
      (node (ref "U$3") (pin "VBUS") (pinfunction "VBUS_VBUS") (pintype "bidirectional"))
    )
    (net (code "204") (name "Net-(L3-L2)") (class "Default")
      (node (ref "L3") (pin "P$2") (pinfunction "L2_P$2") (pintype "passive"))
      (node (ref "VD7") (pin "A") (pinfunction "A_A") (pintype "passive"))
      (node (ref "VT2") (pin "C") (pinfunction "C_C") (pintype "passive"))
    )
    (net (code "205") (name "Net-(LED1-PadC)") (class "Default")
      (node (ref "LED1") (pin "C") (pinfunction "C_C") (pintype "passive"))
      (node (ref "R16") (pin "2") (pinfunction "2_2") (pintype "passive"))
    )
    (net (code "206") (name "Net-(LED2-PadC)") (class "Default")
      (node (ref "LED2") (pin "C") (pinfunction "C_C") (pintype "passive"))
      (node (ref "R15") (pin "2") (pinfunction "2_2") (pintype "passive"))
    )
    (net (code "207") (name "Net-(U$3-MTN1)") (class "Default")
      (node (ref "C40") (pin "1") (pinfunction "1_1") (pintype "passive"))
      (node (ref "R56") (pin "1") (pinfunction "1_1") (pintype "passive"))
      (node (ref "U$3") (pin "MTN1") (pinfunction "MTN2_MTN1") (pintype "bidirectional"))
      (node (ref "U$3") (pin "MTN2") (pinfunction "MTN3_MTN2") (pintype "bidirectional"))
      (node (ref "U$3") (pin "MTN3") (pinfunction "MTN1_MTN3") (pintype "bidirectional"))
      (node (ref "U$3") (pin "MTN4") (pinfunction "MTN4_MTN4") (pintype "bidirectional"))
    )
    (net (code "208") (name "Net-(VT1-D)") (class "Default")
      (node (ref "C26") (pin "1") (pinfunction "1_1") (pintype "passive"))
      (node (ref "C27") (pin "1") (pinfunction "1_1") (pintype "passive"))
      (node (ref "VT1") (pin "3") (pinfunction "D_3") (pintype "passive"))
      (node (ref "X2") (pin "2") (pinfunction "K_2") (pintype "passive"))
    )
    (net (code "209") (name "unconnected-(IC1-CBUS2-Pad13)") (class "Default")
      (node (ref "IC1") (pin "13") (pinfunction "CBUS2_13") (pintype "bidirectional"))
    )
    (net (code "210") (name "unconnected-(IC1-CBUS3-Pad14)") (class "Default")
      (node (ref "IC1") (pin "14") (pinfunction "CBUS3_14") (pintype "bidirectional"))
    )
    (net (code "211") (name "unconnected-(IC1-CBUS4-Pad12)") (class "Default")
      (node (ref "IC1") (pin "12") (pinfunction "CBUS4_12") (pintype "bidirectional"))
    )
    (net (code "212") (name "unconnected-(IC1-OSCI-Pad27)") (class "Default")
      (node (ref "IC1") (pin "27") (pinfunction "OSCI_27") (pintype "input"))
    )
    (net (code "213") (name "unconnected-(IC1-OSCO-Pad28)") (class "Default")
      (node (ref "IC1") (pin "28") (pinfunction "OSCO_28") (pintype "output"))
    )
    (net (code "214") (name "unconnected-(IC1-~{CTS}-Pad11)") (class "Default")
      (node (ref "IC1") (pin "11") (pinfunction "~{CTS}_11") (pintype "input"))
    )
    (net (code "215") (name "unconnected-(IC1-~{DCD}-Pad10)") (class "Default")
      (node (ref "IC1") (pin "10") (pinfunction "~{DCD}_10") (pintype "input"))
    )
    (net (code "216") (name "unconnected-(IC1-~{DSR}-Pad9)") (class "Default")
      (node (ref "IC1") (pin "9") (pinfunction "~{DSR}_9") (pintype "input"))
    )
    (net (code "217") (name "unconnected-(IC1-~{DTR}-Pad2)") (class "Default")
      (node (ref "IC1") (pin "2") (pinfunction "~{DTR}_2") (pintype "output"))
    )
    (net (code "218") (name "unconnected-(IC1-~{RESET}-Pad19)") (class "Default")
      (node (ref "IC1") (pin "19") (pinfunction "~{RESET}_19") (pintype "input"))
    )
    (net (code "219") (name "unconnected-(IC1-~{RI}-Pad6)") (class "Default")
      (node (ref "IC1") (pin "6") (pinfunction "~{RI}_6") (pintype "input"))
    )
    (net (code "220") (name "unconnected-(IC1-~{RTS}-Pad3)") (class "Default")
      (node (ref "IC1") (pin "3") (pinfunction "~{RTS}_3") (pintype "output"))
    )
    (net (code "221") (name "unconnected-(J1AN-MS-Pad45)") (class "Default")
      (node (ref "J1") (pin "45") (pinfunction "MS_45") (pintype "passive"))
    )
    (net (code "222") (name "unconnected-(J1AR-MS-Pad49)") (class "Default")
      (node (ref "J1") (pin "49") (pinfunction "MS_49") (pintype "passive"))
    )
    (net (code "223") (name "unconnected-(J1AT-MS-Pad50)") (class "Default")
      (node (ref "J1") (pin "50") (pinfunction "MS_50") (pintype "passive"))
    )
    (net (code "224") (name "unconnected-(SA1-RESERVE-PadJP1_1)") (class "Default")
      (node (ref "SA1") (pin "JP1_1") (pinfunction "RESERVE_JP1_1") (pintype "no_connect"))
    )
    (net (code "225") (name "unconnected-(SA1-RESERVE1-PadJP1_3)") (class "Default")
      (node (ref "SA1") (pin "JP1_3") (pinfunction "RESERVE1_JP1_3") (pintype "no_connect"))
    )
    (net (code "226") (name "unconnected-(SA1-RESERVE2-PadJP1_2)") (class "Default")
      (node (ref "SA1") (pin "JP1_2") (pinfunction "RESERVE2_JP1_2") (pintype "no_connect"))
    )
    (net (code "227") (name "unconnected-(SA1-RESERVE3-PadJP1_4)") (class "Default")
      (node (ref "SA1") (pin "JP1_4") (pinfunction "RESERVE3_JP1_4") (pintype "no_connect"))
    )
    (net (code "228") (name "unconnected-(SA1-RESERVE4-PadJP1_6)") (class "Default")
      (node (ref "SA1") (pin "JP1_6") (pinfunction "RESERVE4_JP1_6") (pintype "no_connect"))
    )
    (net (code "229") (name "unconnected-(SA1-RESERVE5-PadJP1_8)") (class "Default")
      (node (ref "SA1") (pin "JP1_8") (pinfunction "RESERVE5_JP1_8") (pintype "no_connect"))
    )
    (net (code "230") (name "unconnected-(SA1-RESERVE6-PadJP1_35)") (class "Default")
      (node (ref "SA1") (pin "JP1_35") (pinfunction "RESERVE6_JP1_35") (pintype "no_connect"))
    )
    (net (code "231") (name "unconnected-(SA1-RESERVE7-PadJP2_60)") (class "Default")
      (node (ref "SA1") (pin "JP2_60") (pinfunction "RESERVE7_JP2_60") (pintype "no_connect"))
    )
    (net (code "232") (name "unconnected-(SA1-~{CS0}-PadJP1_41)") (class "Default")
      (node (ref "SA1") (pin "JP1_41") (pinfunction "~{CS0}_JP1_41") (pintype "output"))
    )
    (net (code "233") (name "unconnected-(SA1-~{CS1}-PadJP1_42)") (class "Default")
      (node (ref "SA1") (pin "JP1_42") (pinfunction "~{CS1}_JP1_42") (pintype "output"))
    )
    (net (code "234") (name "unconnected-(U$3-PadID)") (class "Default")
      (node (ref "U$3") (pin "ID") (pinfunction "ID_ID") (pintype "bidirectional"))
    )
  )
)
